# nixie_schema.net
KiCad netlist of a schematic drawn in EAGLE
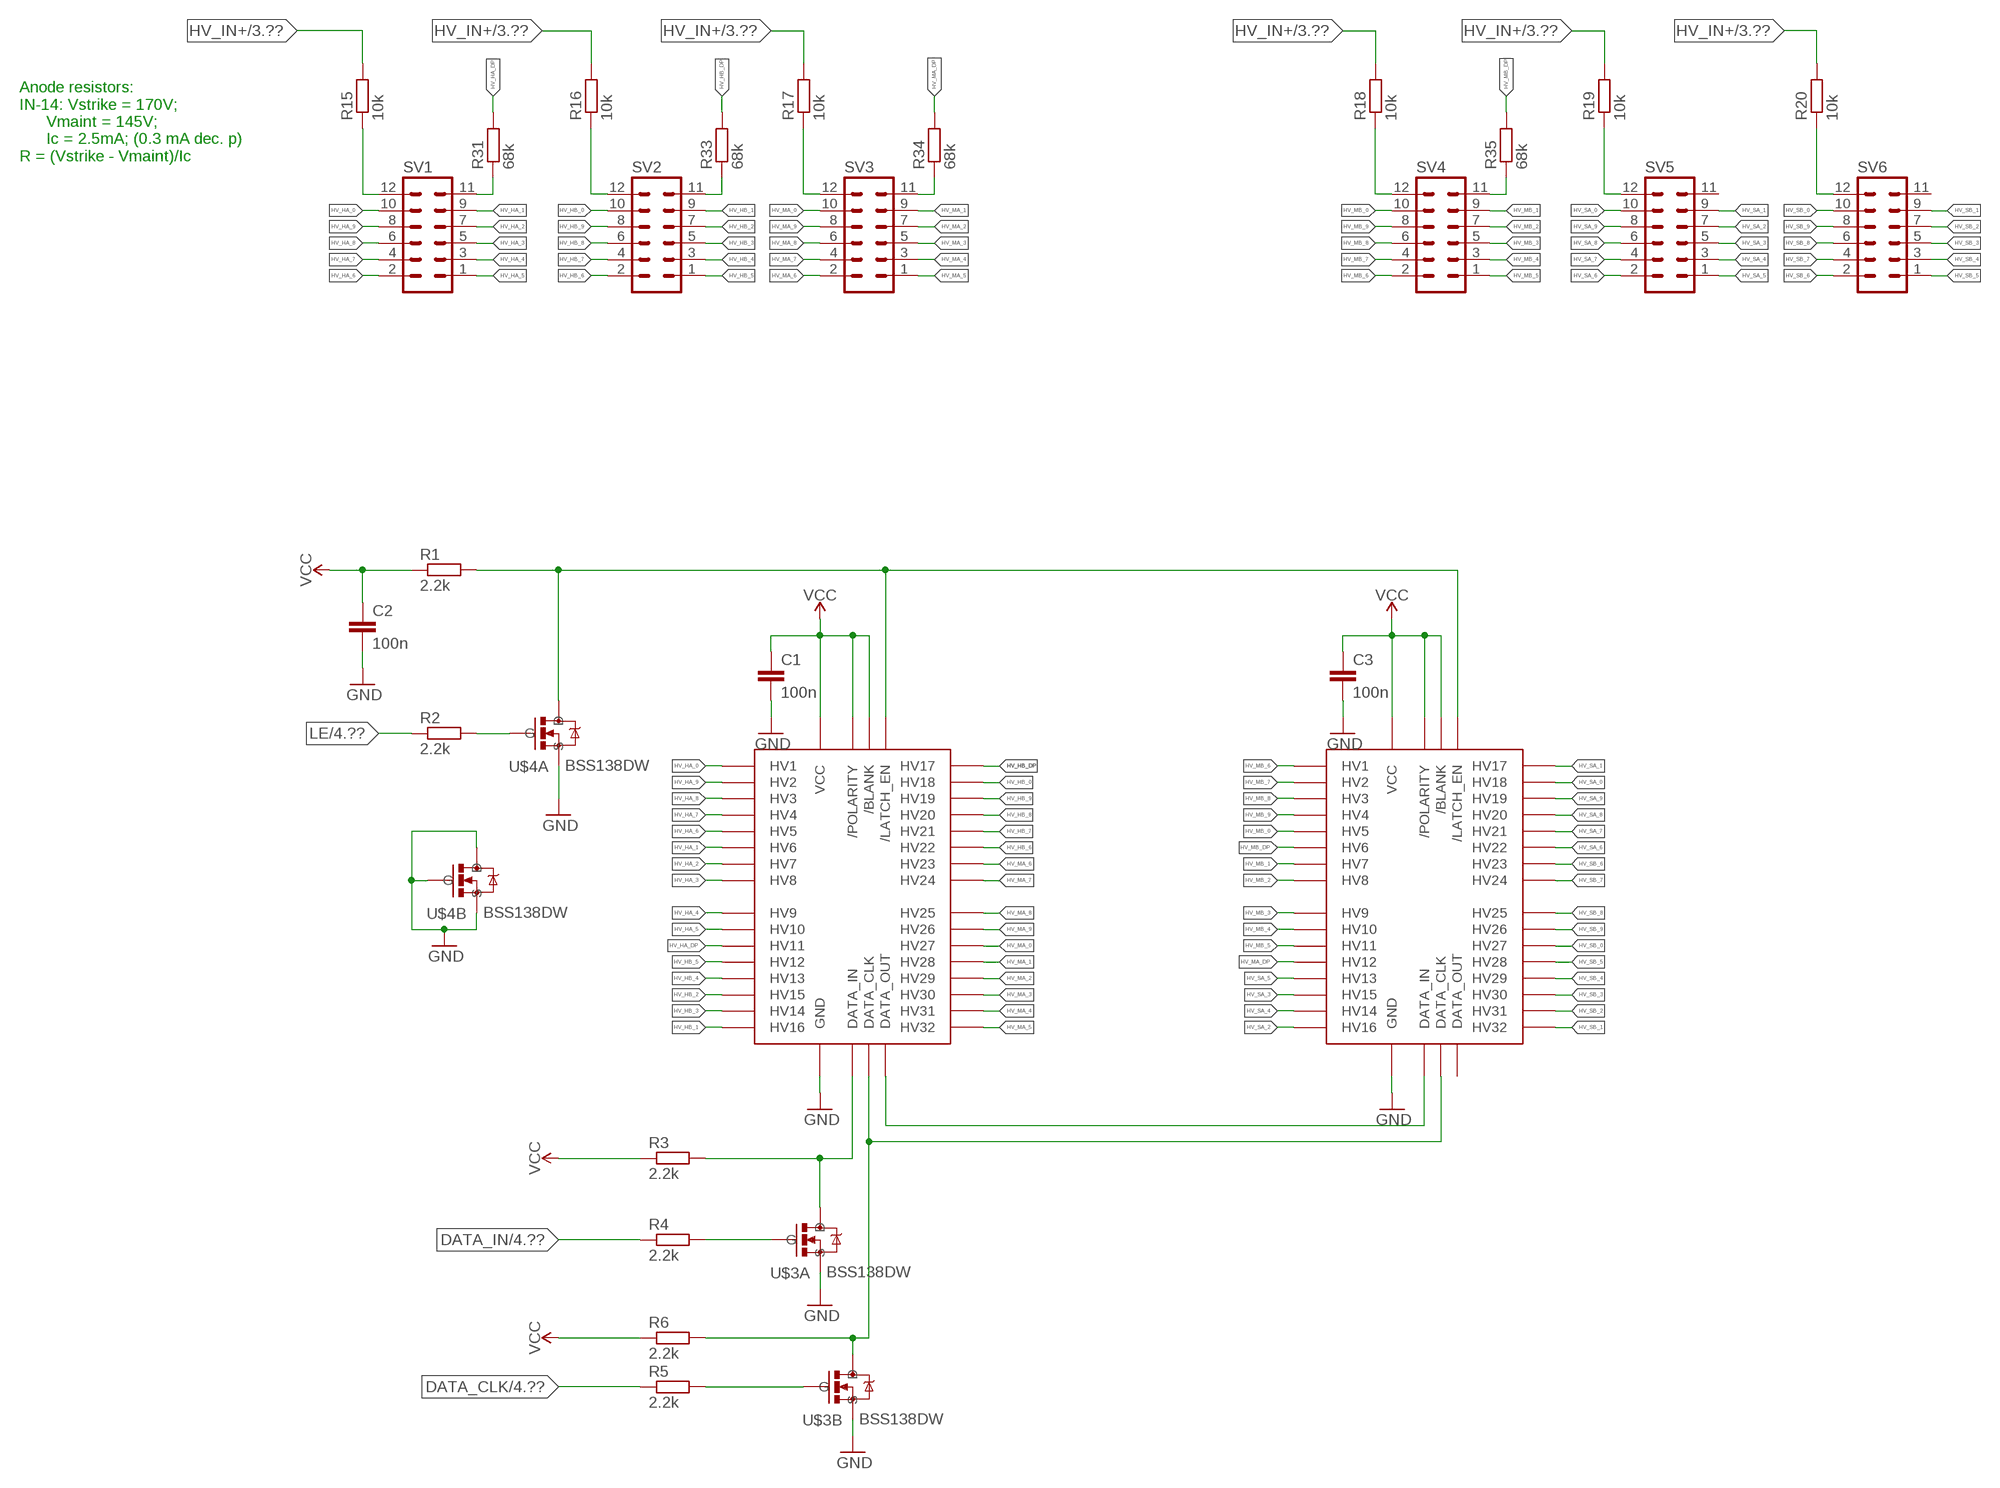
[diagram p0: schematic, sheet 1]
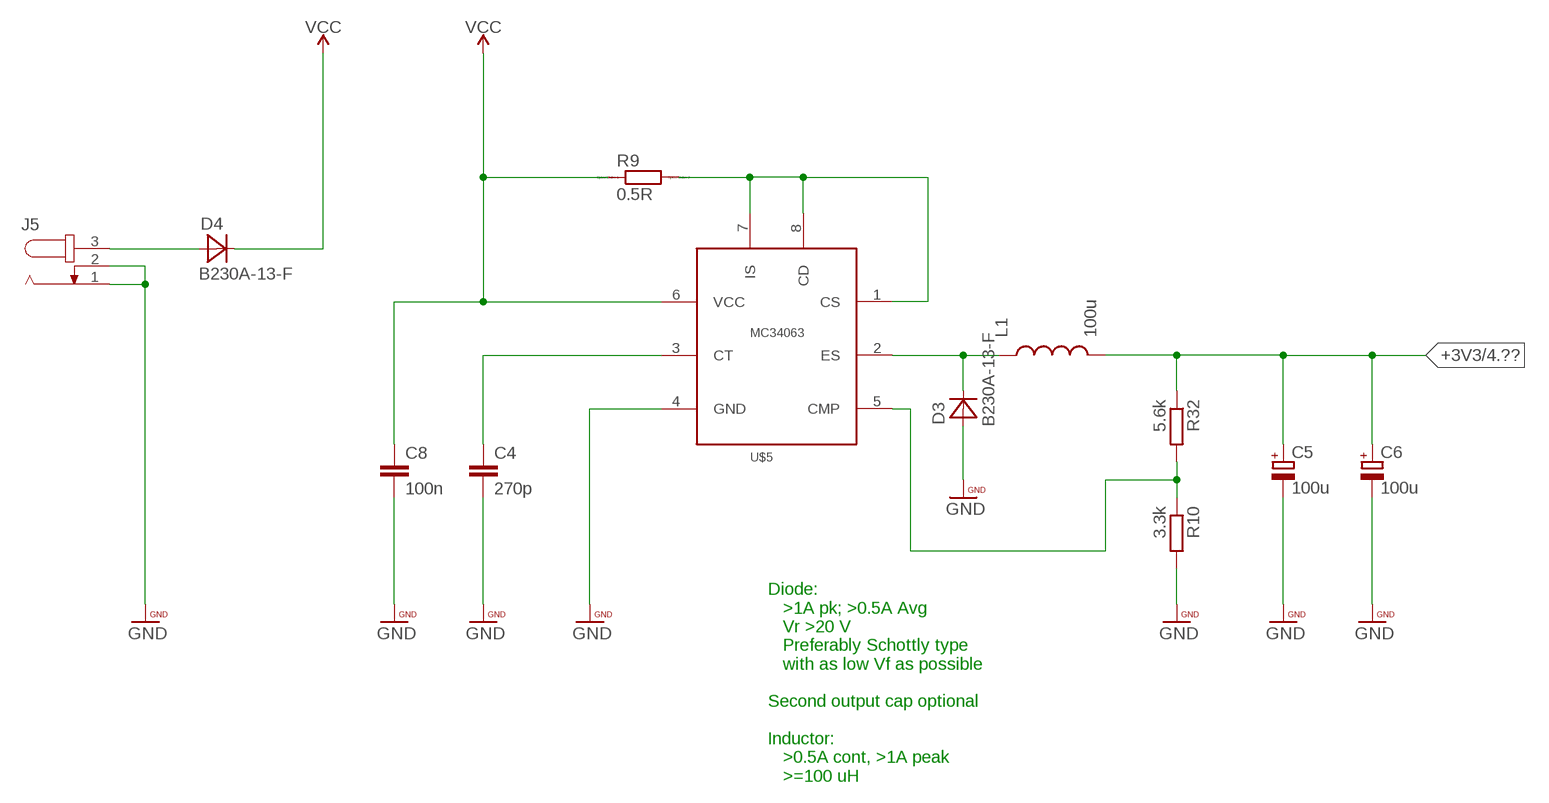
[diagram p1: schematic, sheet 2]
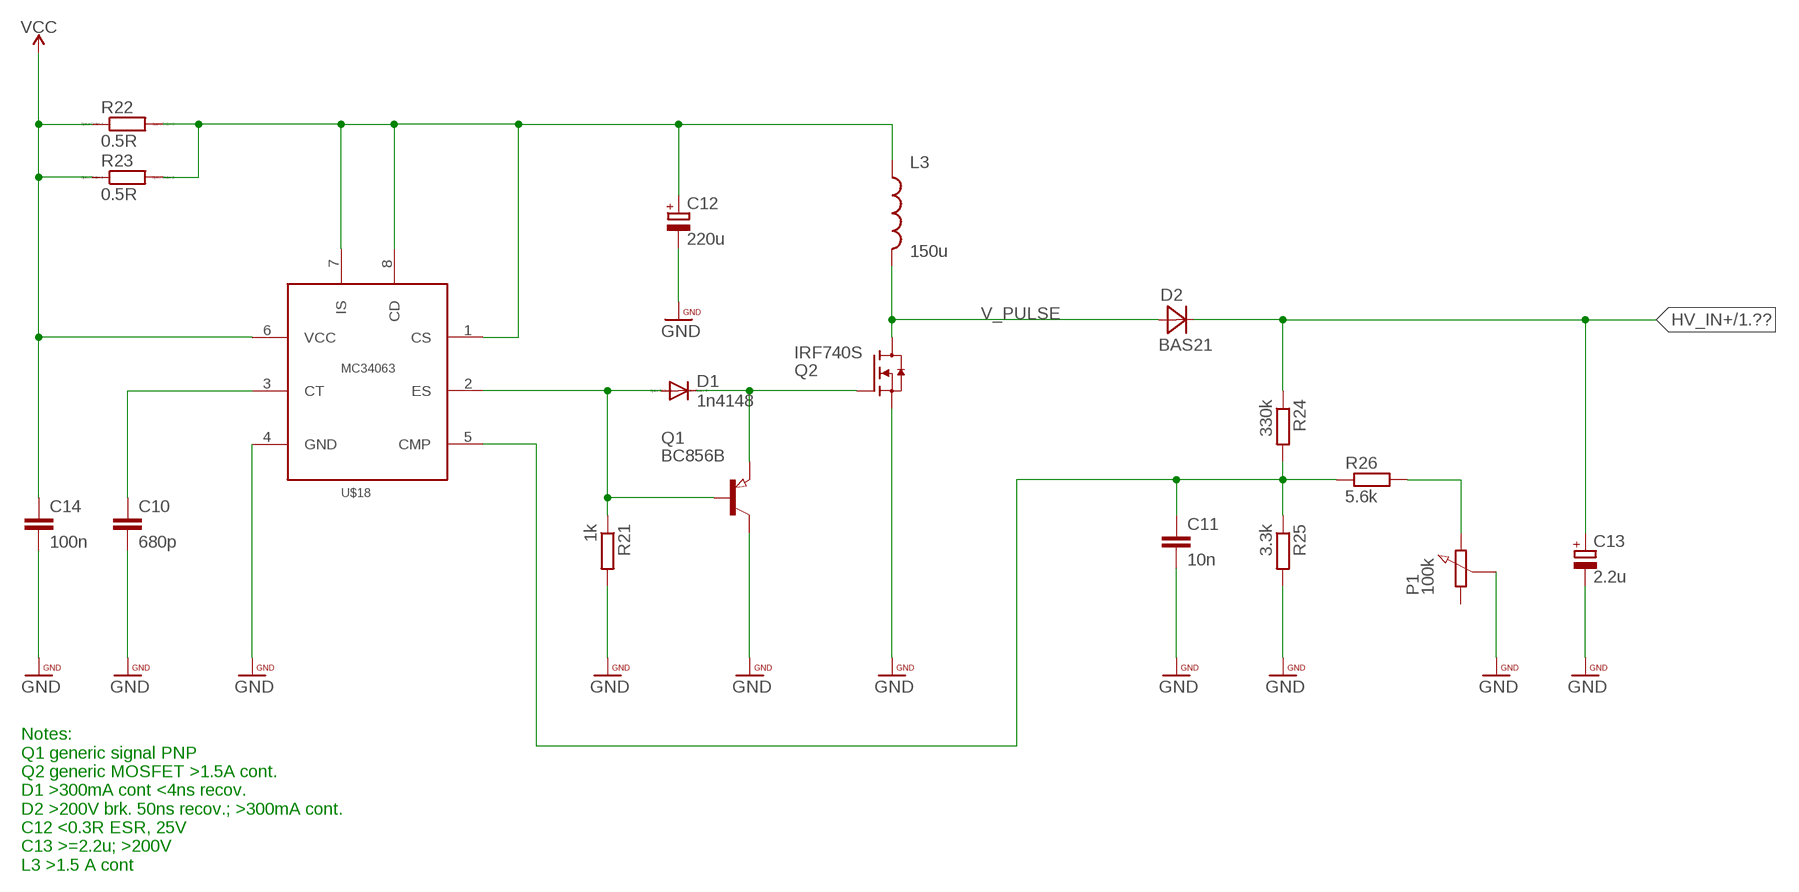
[diagram p2: schematic, sheet 3]
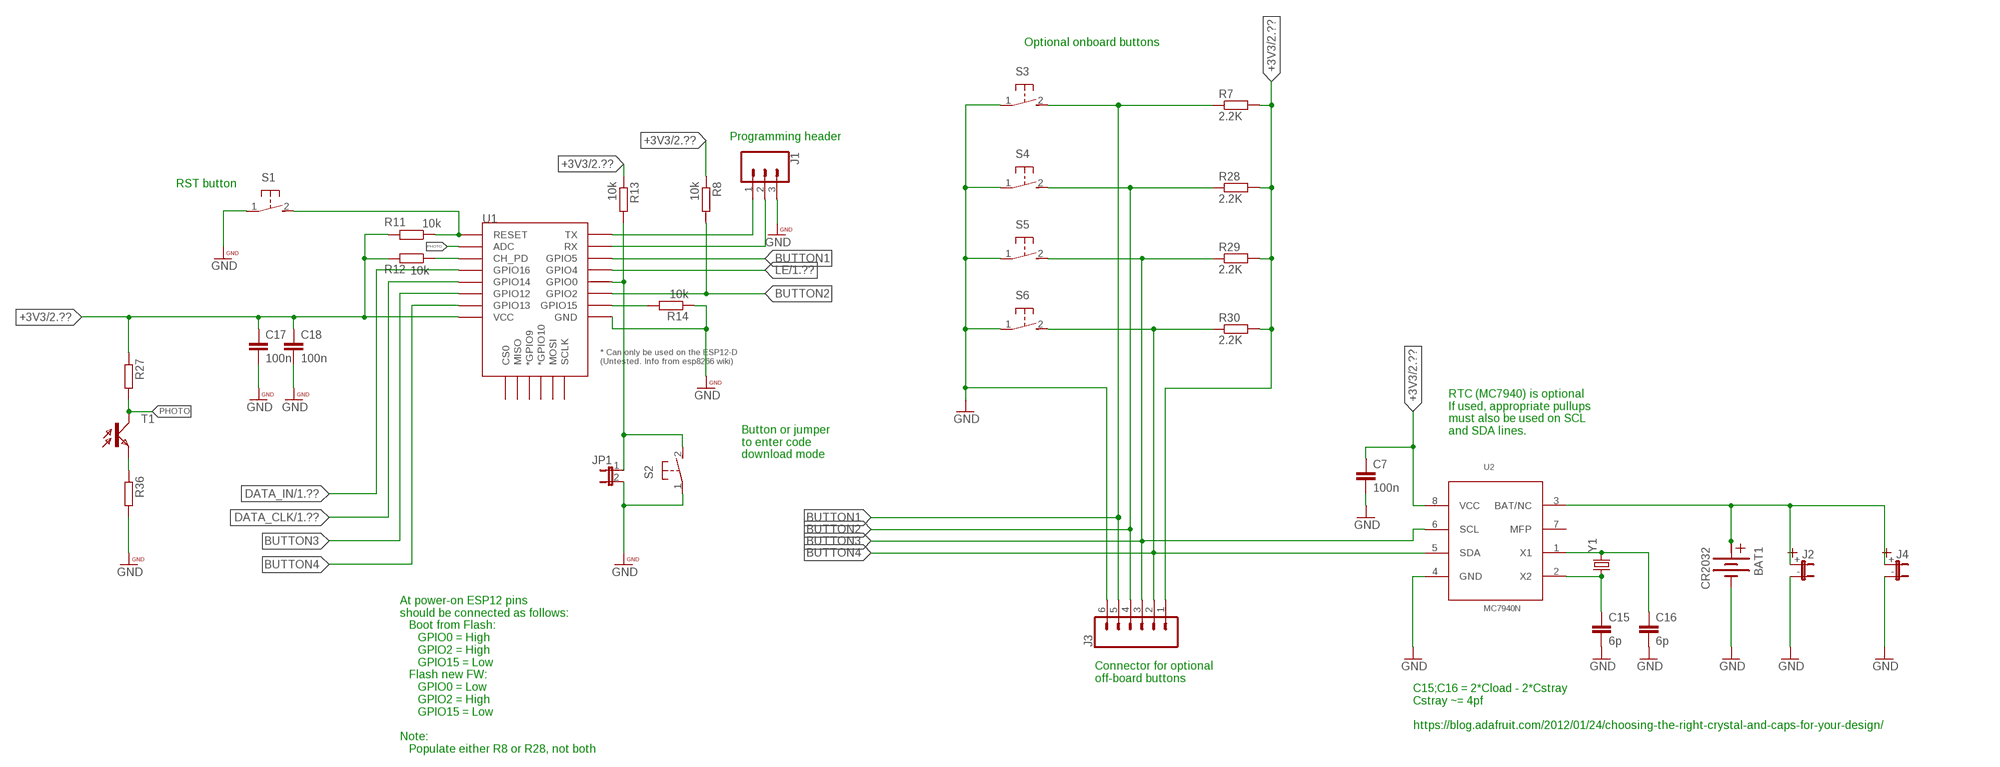
[diagram p3: schematic, sheet 4]
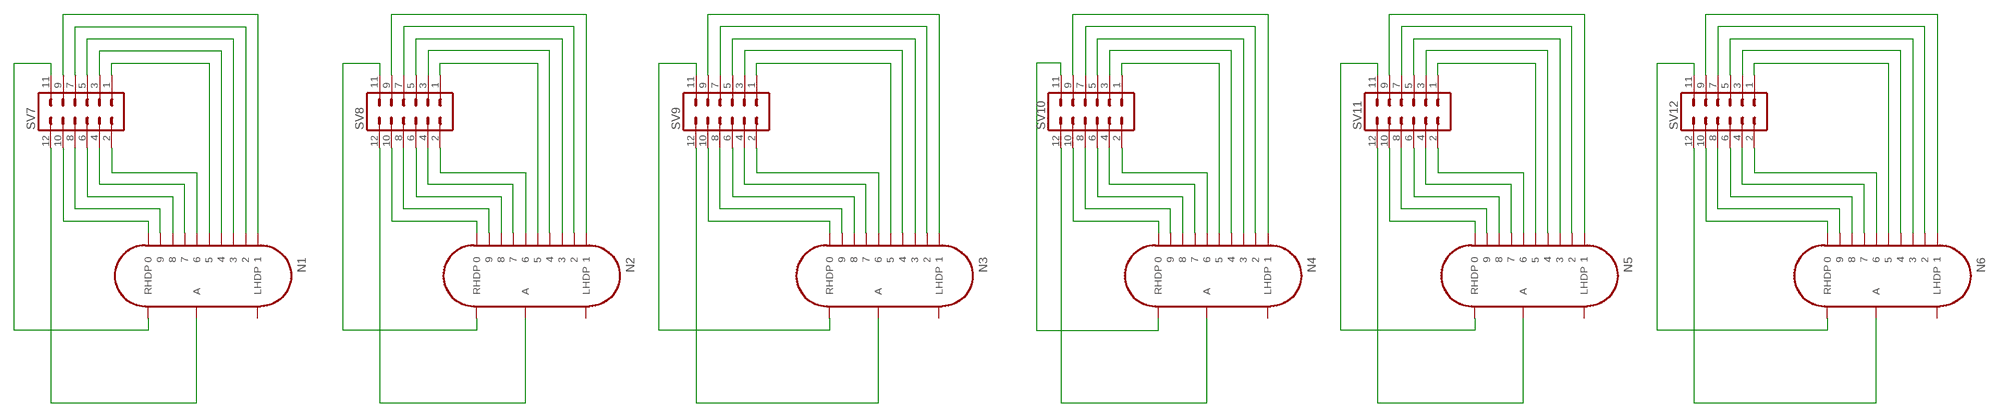
[diagram p4: schematic, sheet 5]

(export (version "E")
  (design (tool "Eeschema 10.0.6"))
  (components
    (comp (ref "C1")
      (value "100n")
      (footprint "eagle-import:C0805")
      (libsource (lib "eagle-import") (part "C-EUC0805"))
    )
    (comp (ref "C2")
      (value "100n")
      (footprint "eagle-import:C0805")
      (libsource (lib "eagle-import") (part "C-EUC0805"))
    )
    (comp (ref "C3")
      (value "100n")
      (footprint "eagle-import:C0805")
      (libsource (lib "eagle-import") (part "C-EUC0805"))
    )
    (comp (ref "R1")
      (value "2.2k")
      (footprint "eagle-import:R0603")
      (libsource (lib "eagle-import") (part "R-EU_R0603"))
    )
    (comp (ref "R2")
      (value "2.2k")
      (footprint "eagle-import:R0603")
      (libsource (lib "eagle-import") (part "R-EU_R0603"))
    )
    (comp (ref "R3")
      (value "2.2k")
      (footprint "eagle-import:R0603")
      (libsource (lib "eagle-import") (part "R-EU_R0603"))
    )
    (comp (ref "R4")
      (value "2.2k")
      (footprint "eagle-import:R0603")
      (libsource (lib "eagle-import") (part "R-EU_R0603"))
    )
    (comp (ref "R5")
      (value "2.2k")
      (footprint "eagle-import:R0603")
      (libsource (lib "eagle-import") (part "R-EU_R0603"))
    )
    (comp (ref "R6")
      (value "2.2k")
      (footprint "eagle-import:R0603")
      (libsource (lib "eagle-import") (part "R-EU_R0603"))
    )
    (comp (ref "R15")
      (value "10k")
      (footprint "eagle-import:R0603")
      (libsource (lib "eagle-import") (part "R-EU_R0603"))
    )
    (comp (ref "R16")
      (value "10k")
      (footprint "eagle-import:R0603")
      (libsource (lib "eagle-import") (part "R-EU_R0603"))
    )
    (comp (ref "R17")
      (value "10k")
      (footprint "eagle-import:R0603")
      (libsource (lib "eagle-import") (part "R-EU_R0603"))
    )
    (comp (ref "R18")
      (value "10k")
      (footprint "eagle-import:R0603")
      (libsource (lib "eagle-import") (part "R-EU_R0603"))
    )
    (comp (ref "R19")
      (value "10k")
      (footprint "eagle-import:R0603")
      (libsource (lib "eagle-import") (part "R-EU_R0603"))
    )
    (comp (ref "R20")
      (value "10k")
      (footprint "eagle-import:R0603")
      (libsource (lib "eagle-import") (part "R-EU_R0603"))
    )
    (comp (ref "R31")
      (value "68k")
      (footprint "eagle-import:R0603")
      (libsource (lib "eagle-import") (part "R-EU_R0603"))
    )
    (comp (ref "R33")
      (value "68k")
      (footprint "eagle-import:R0603")
      (libsource (lib "eagle-import") (part "R-EU_R0603"))
    )
    (comp (ref "R34")
      (value "68k")
      (footprint "eagle-import:R0603")
      (libsource (lib "eagle-import") (part "R-EU_R0603"))
    )
    (comp (ref "R35")
      (value "68k")
      (footprint "eagle-import:R0603")
      (libsource (lib "eagle-import") (part "R-EU_R0603"))
    )
    (comp (ref "SV1")
      (value "MA06-2")
      (footprint "eagle-import:MA06-2")
      (libsource (lib "eagle-import") (part "MA06-2"))
    )
    (comp (ref "SV2")
      (value "MA06-2")
      (footprint "eagle-import:MA06-2")
      (libsource (lib "eagle-import") (part "MA06-2"))
    )
    (comp (ref "SV3")
      (value "MA06-2")
      (footprint "eagle-import:MA06-2")
      (libsource (lib "eagle-import") (part "MA06-2"))
    )
    (comp (ref "SV4")
      (value "MA06-2")
      (footprint "eagle-import:MA06-2")
      (libsource (lib "eagle-import") (part "MA06-2"))
    )
    (comp (ref "SV5")
      (value "MA06-2")
      (footprint "eagle-import:MA06-2")
      (libsource (lib "eagle-import") (part "MA06-2"))
    )
    (comp (ref "SV6")
      (value "MA06-2")
      (footprint "eagle-import:MA06-2")
      (libsource (lib "eagle-import") (part "MA06-2"))
    )
    (comp (ref "U$1")
      (value "HV5522")
      (footprint "eagle-import:CQFP-44")
      (libsource (lib "eagle-import") (part "HV5522"))
    )
    (comp (ref "U$2")
      (value "HV5522")
      (footprint "eagle-import:CQFP-44")
      (libsource (lib "eagle-import") (part "HV5522"))
    )
    (comp (ref "U$3")
      (value "BSS138DW")
      (footprint "eagle-import:SOT-363")
      (libsource (lib "eagle-import") (part "BSS138DW"))
    )
    (comp (ref "U$4")
      (value "BSS138DW")
      (footprint "eagle-import:SOT-363")
      (libsource (lib "eagle-import") (part "BSS138DW"))
    )
    (comp (ref "BAT1")
      (value "CR2032")
      (footprint "eagle-import:CR2032")
      (libsource (lib "eagle-import") (part "CR2032"))
    )
    (comp (ref "C7")
      (value "100n")
      (footprint "eagle-import:C0805")
      (libsource (lib "eagle-import") (part "C-EUC0805"))
    )
    (comp (ref "C15")
      (value "6p")
      (footprint "eagle-import:C0805")
      (libsource (lib "eagle-import") (part "C-EUC0805"))
    )
    (comp (ref "C16")
      (value "6p")
      (footprint "eagle-import:C0805")
      (libsource (lib "eagle-import") (part "C-EUC0805"))
    )
    (comp (ref "C17")
      (value "100n")
      (footprint "eagle-import:C0805")
      (libsource (lib "eagle-import") (part "C-EUC0805"))
    )
    (comp (ref "C18")
      (value "100n")
      (footprint "eagle-import:C0805")
      (libsource (lib "eagle-import") (part "C-EUC0805"))
    )
    (comp (ref "J1")
      (value "CONN_03")
      (footprint "eagle-import:1X03")
      (libsource (lib "eagle-import") (part "CONN_03"))
    )
    (comp (ref "J2")
      (value "RTC_CONSMD")
      (footprint "eagle-import:PICOBLADE_SMD_2")
      (libsource (lib "eagle-import") (part "RTC_CONSMD"))
    )
    (comp (ref "J3")
      (value "CONN_06NO_SILK_FEMALE_PTH")
      (footprint "eagle-import:1X06_NO_SILK")
      (libsource (lib "eagle-import") (part "CONN_06NO_SILK_FEMALE_PTH"))
    )
    (comp (ref "J4")
      (value "RTC_CONTHT")
      (footprint "eagle-import:PICOBLADE_THT_2")
      (libsource (lib "eagle-import") (part "RTC_CONTHT"))
    )
    (comp (ref "JP1")
      (value "JUMPER2")
      (footprint "eagle-import:JUMPER2")
      (libsource (lib "eagle-import") (part "JUMPER2"))
    )
    (comp (ref "R7")
      (value "2.2K")
      (footprint "eagle-import:R0603")
      (libsource (lib "eagle-import") (part "R-EU_R0603"))
    )
    (comp (ref "R8")
      (value "10k")
      (footprint "eagle-import:R0603")
      (libsource (lib "eagle-import") (part "resistor_R-EU_R0603"))
    )
    (comp (ref "R11")
      (value "10k")
      (footprint "eagle-import:R0603")
      (libsource (lib "eagle-import") (part "resistor_R-EU_R0603"))
    )
    (comp (ref "R12")
      (value "10k")
      (footprint "eagle-import:R0603")
      (libsource (lib "eagle-import") (part "resistor_R-EU_R0603"))
    )
    (comp (ref "R13")
      (value "10k")
      (footprint "eagle-import:R0603")
      (libsource (lib "eagle-import") (part "resistor_R-EU_R0603"))
    )
    (comp (ref "R14")
      (value "10k")
      (footprint "eagle-import:R0603")
      (libsource (lib "eagle-import") (part "resistor_R-EU_R0603"))
    )
    (comp (ref "R27")
      (value "R-EU_R0603")
      (footprint "eagle-import:R0603")
      (libsource (lib "eagle-import") (part "resistor_R-EU_R0603"))
    )
    (comp (ref "R28")
      (value "2.2K")
      (footprint "eagle-import:R0603")
      (libsource (lib "eagle-import") (part "R-EU_R0603"))
    )
    (comp (ref "R29")
      (value "2.2K")
      (footprint "eagle-import:R0603")
      (libsource (lib "eagle-import") (part "R-EU_R0603"))
    )
    (comp (ref "R30")
      (value "2.2K")
      (footprint "eagle-import:R0603")
      (libsource (lib "eagle-import") (part "R-EU_R0603"))
    )
    (comp (ref "R36")
      (value "R-EU_R0603")
      (footprint "eagle-import:R0603")
      (libsource (lib "eagle-import") (part "resistor_R-EU_R0603"))
    )
    (comp (ref "S1")
      (value "31-XX")
      (footprint "eagle-import:B3F-31XX")
      (fields (field (name "MPN") "B3F-3100"))
      (libsource (lib "eagle-import") (part "31-XX"))
    )
    (comp (ref "S2")
      (value "31-XX")
      (footprint "eagle-import:B3F-31XX")
      (fields (field (name "MPN") "B3F-3100"))
      (libsource (lib "eagle-import") (part "31-XX"))
    )
    (comp (ref "S3")
      (value "31-XX")
      (footprint "eagle-import:B3F-31XX")
      (fields (field (name "MPN") "B3F-3100"))
      (libsource (lib "eagle-import") (part "31-XX"))
    )
    (comp (ref "S4")
      (value "31-XX")
      (footprint "eagle-import:B3F-31XX")
      (fields (field (name "MPN") "B3F-3100"))
      (libsource (lib "eagle-import") (part "31-XX"))
    )
    (comp (ref "S5")
      (value "31-XX")
      (footprint "eagle-import:B3F-31XX")
      (fields (field (name "MPN") "B3F-3100"))
      (libsource (lib "eagle-import") (part "31-XX"))
    )
    (comp (ref "S6")
      (value "31-XX")
      (footprint "eagle-import:B3F-31XX")
      (fields (field (name "MPN") "B3F-3100"))
      (libsource (lib "eagle-import") (part "31-XX"))
    )
    (comp (ref "T1")
      (value "PHOTO_TRANS")
      (footprint "eagle-import:C0805K")
      (libsource (lib "eagle-import") (part "PHOTO_TRANS"))
    )
    (comp (ref "U1")
      (value "ESP12ESMD")
      (footprint "eagle-import:ESP12E-SMD")
      (libsource (lib "eagle-import") (part "ESP12ESMD"))
    )
    (comp (ref "U2")
      (value "MC7940N")
      (footprint "eagle-import:SOIC8-N_MC")
      (libsource (lib "eagle-import") (part "MC7940N"))
    )
    (comp (ref "Y1")
      (value "ECS-.327-7-34B")
      (footprint "eagle-import:CRYSTAL_PACK")
      (libsource (lib "eagle-import") (part "ECS-.327-7-34B"))
    )
    (comp (ref "C4")
      (value "270p")
      (footprint "eagle-import:C0805")
      (libsource (lib "eagle-import") (part "C-EUC0805"))
    )
    (comp (ref "C5")
      (value "100u")
      (footprint "eagle-import:153CLV-1014")
      (libsource (lib "eagle-import") (part "CPOL-EU153CLV-1014"))
    )
    (comp (ref "C6")
      (value "100u")
      (footprint "eagle-import:153CLV-1014")
      (libsource (lib "eagle-import") (part "CPOL-EU153CLV-1014"))
    )
    (comp (ref "C8")
      (value "100n")
      (footprint "eagle-import:C0805")
      (libsource (lib "eagle-import") (part "C-EUC0805"))
    )
    (comp (ref "D3")
      (value "B230A-13-F")
      (footprint "eagle-import:SMA_SMB")
      (libsource (lib "eagle-import") (part "B230A-13-F"))
    )
    (comp (ref "D4")
      (value "B230A-13-F")
      (footprint "eagle-import:SMA_SMB")
      (libsource (lib "eagle-import") (part "B230A-13-F"))
    )
    (comp (ref "J5")
      (value "JACK-PLUG0")
      (footprint "eagle-import:SPC4077")
      (libsource (lib "eagle-import") (part "JACK-PLUG0"))
    )
    (comp (ref "L1")
      (value "100u")
      (footprint "eagle-import:INDUCTOR_PACKAGE")
      (libsource (lib "eagle-import") (part "HM78D-128151KLFTR"))
    )
    (comp (ref "R9")
      (value "0.5R")
      (footprint "eagle-import:R1210")
      (libsource (lib "eagle-import") (part "RR1210"))
    )
    (comp (ref "R10")
      (value "3.3k")
      (footprint "eagle-import:R0603")
      (libsource (lib "eagle-import") (part "resistor_R-EU_R0603"))
    )
    (comp (ref "R32")
      (value "5.6k")
      (footprint "eagle-import:R0603")
      (libsource (lib "eagle-import") (part "resistor_R-EU_R0603"))
    )
    (comp (ref "U$5")
      (value "MC34063")
      (footprint "eagle-import:SOIC08")
      (libsource (lib "eagle-import") (part "MC34063"))
    )
    (comp (ref "N1")
      (value "IN-14_FIXED")
      (footprint "eagle-import:IN-14")
      (libsource (lib "eagle-import") (part "IN-14_FIXED"))
    )
    (comp (ref "N2")
      (value "IN-14_FIXED")
      (footprint "eagle-import:IN-14")
      (libsource (lib "eagle-import") (part "IN-14_FIXED"))
    )
    (comp (ref "N3")
      (value "IN-14_FIXED")
      (footprint "eagle-import:IN-14")
      (libsource (lib "eagle-import") (part "IN-14_FIXED"))
    )
    (comp (ref "N4")
      (value "IN-14_FIXED")
      (footprint "eagle-import:IN-14")
      (libsource (lib "eagle-import") (part "IN-14_FIXED"))
    )
    (comp (ref "N5")
      (value "IN-14_FIXED")
      (footprint "eagle-import:IN-14")
      (libsource (lib "eagle-import") (part "IN-14_FIXED"))
    )
    (comp (ref "N6")
      (value "IN-14_FIXED")
      (footprint "eagle-import:IN-14")
      (libsource (lib "eagle-import") (part "IN-14_FIXED"))
    )
    (comp (ref "SV7")
      (value "MA06-2")
      (footprint "eagle-import:MA06-2")
      (libsource (lib "eagle-import") (part "MA06-2"))
    )
    (comp (ref "SV8")
      (value "MA06-2")
      (footprint "eagle-import:MA06-2")
      (libsource (lib "eagle-import") (part "MA06-2"))
    )
    (comp (ref "SV9")
      (value "MA06-2")
      (footprint "eagle-import:MA06-2")
      (libsource (lib "eagle-import") (part "MA06-2"))
    )
    (comp (ref "SV10")
      (value "MA06-2")
      (footprint "eagle-import:MA06-2")
      (libsource (lib "eagle-import") (part "MA06-2"))
    )
    (comp (ref "SV11")
      (value "MA06-2")
      (footprint "eagle-import:MA06-2")
      (libsource (lib "eagle-import") (part "MA06-2"))
    )
    (comp (ref "SV12")
      (value "MA06-2")
      (footprint "eagle-import:MA06-2")
      (libsource (lib "eagle-import") (part "MA06-2"))
    )
    (comp (ref "C10")
      (value "680p")
      (footprint "eagle-import:C0805")
      (libsource (lib "eagle-import") (part "C-EUC0805"))
    )
    (comp (ref "C11")
      (value "10n")
      (footprint "eagle-import:C0805")
      (libsource (lib "eagle-import") (part "C-EUC0805"))
    )
    (comp (ref "C12")
      (value "220u")
      (footprint "eagle-import:153CLV-1014")
      (libsource (lib "eagle-import") (part "CPOL-EU153CLV-1014"))
    )
    (comp (ref "C13")
      (value "2.2u")
      (footprint "eagle-import:153CLV-1014")
      (libsource (lib "eagle-import") (part "CPOL-EU153CLV-1014"))
    )
    (comp (ref "C14")
      (value "100n")
      (footprint "eagle-import:C0805")
      (libsource (lib "eagle-import") (part "C-EUC0805"))
    )
    (comp (ref "D1")
      (value "1n4148")
      (footprint "eagle-import:SOD123")
      (libsource (lib "eagle-import") (part "DIODE-SOD123"))
    )
    (comp (ref "D2")
      (value "BAS21")
      (footprint "eagle-import:SOT23")
      (libsource (lib "eagle-import") (part "BAS21"))
    )
    (comp (ref "L3")
      (value "150u")
      (footprint "eagle-import:INDUCTOR_PACKAGE")
      (libsource (lib "eagle-import") (part "HM78D-128151KLFTR"))
    )
    (comp (ref "P1")
      (value "100k")
      (footprint "eagle-import:UNI_POT_SMD")
      (libsource (lib "eagle-import") (part "UNIVERSAL-POTENTIOMETER_SMD"))
    )
    (comp (ref "Q1")
      (value "BC856B")
      (footprint "eagle-import:SOT23")
      (libsource (lib "eagle-import") (part "BC856B"))
    )
    (comp (ref "Q2")
      (value "IRF740S")
      (footprint "eagle-import:D2PACK")
      (libsource (lib "eagle-import") (part "IRF740S"))
    )
    (comp (ref "R21")
      (value "1k")
      (footprint "eagle-import:R0603")
      (libsource (lib "eagle-import") (part "resistor_R-EU_R0603"))
    )
    (comp (ref "R22")
      (value "0.5R")
      (footprint "eagle-import:R1210")
      (libsource (lib "eagle-import") (part "RR1210"))
    )
    (comp (ref "R23")
      (value "0.5R")
      (footprint "eagle-import:R1210")
      (libsource (lib "eagle-import") (part "RR1210"))
    )
    (comp (ref "R24")
      (value "330k")
      (footprint "eagle-import:R0603")
      (libsource (lib "eagle-import") (part "resistor_R-EU_R0603"))
    )
    (comp (ref "R25")
      (value "3.3k")
      (footprint "eagle-import:R0603")
      (libsource (lib "eagle-import") (part "resistor_R-EU_R0603"))
    )
    (comp (ref "R26")
      (value "5.6k")
      (footprint "eagle-import:R0603")
      (libsource (lib "eagle-import") (part "resistor_R-EU_R0603"))
    )
    (comp (ref "U$18")
      (value "MC34063")
      (footprint "eagle-import:SOIC08")
      (libsource (lib "eagle-import") (part "MC34063"))
    )
  )
  (nets
    (net (code "1") (name "+") (class "Default")
      (node (ref "BAT1") (pin "+_2") (pinfunction "+_+_2") (pintype "power_in"))
    )
    (net (code "2") (name "+3V3") (class "Default")
      (node (ref "C17") (pin "1") (pinfunction "1_1") (pintype "passive"))
      (node (ref "C18") (pin "1") (pinfunction "1_1") (pintype "passive"))
      (node (ref "C5") (pin "+") (pinfunction "+_+") (pintype "passive"))
      (node (ref "C6") (pin "+") (pinfunction "+_+") (pintype "passive"))
      (node (ref "C7") (pin "1") (pinfunction "1_1") (pintype "passive"))
      (node (ref "J3") (pin "1") (pinfunction "1_1") (pintype "passive"))
      (node (ref "L1") (pin "P$2") (pinfunction "2_P$2") (pintype "passive"))
      (node (ref "R11") (pin "2") (pinfunction "2_2") (pintype "passive"))
      (node (ref "R12") (pin "2") (pinfunction "2_2") (pintype "passive"))
      (node (ref "R13") (pin "1") (pinfunction "1_1") (pintype "passive"))
      (node (ref "R27") (pin "1") (pinfunction "1_1") (pintype "passive"))
      (node (ref "R28") (pin "2") (pinfunction "2_2") (pintype "passive"))
      (node (ref "R29") (pin "2") (pinfunction "2_2") (pintype "passive"))
      (node (ref "R30") (pin "2") (pinfunction "2_2") (pintype "passive"))
      (node (ref "R32") (pin "1") (pinfunction "1_1") (pintype "passive"))
      (node (ref "R7") (pin "2") (pinfunction "2_2") (pintype "passive"))
      (node (ref "R8") (pin "1") (pinfunction "1_1") (pintype "passive"))
      (node (ref "U1") (pin "VCC") (pinfunction "VCC_VCC") (pintype "bidirectional"))
      (node (ref "U2") (pin "8") (pinfunction "VCC_8") (pintype "bidirectional"))
    )
    (net (code "3") (name "BUTTON1") (class "Default")
      (node (ref "J3") (pin "5") (pinfunction "5_5") (pintype "passive"))
      (node (ref "R7") (pin "1") (pinfunction "1_1") (pintype "passive"))
      (node (ref "S3") (pin "2") (pinfunction "S_2") (pintype "passive"))
      (node (ref "U1") (pin "GPIO5") (pinfunction "GPIO5_GPIO5") (pintype "bidirectional"))
    )
    (net (code "4") (name "BUTTON2") (class "Default")
      (node (ref "J3") (pin "4") (pinfunction "4_4") (pintype "passive"))
      (node (ref "R28") (pin "1") (pinfunction "1_1") (pintype "passive"))
      (node (ref "R8") (pin "2") (pinfunction "2_2") (pintype "passive"))
      (node (ref "S4") (pin "2") (pinfunction "S_2") (pintype "passive"))
      (node (ref "U1") (pin "GPIO2") (pinfunction "GPIO2_GPIO2") (pintype "bidirectional"))
    )
    (net (code "5") (name "BUTTON3") (class "Default")
      (node (ref "J3") (pin "3") (pinfunction "3_3") (pintype "passive"))
      (node (ref "R29") (pin "1") (pinfunction "1_1") (pintype "passive"))
      (node (ref "S5") (pin "2") (pinfunction "S_2") (pintype "passive"))
      (node (ref "U1") (pin "GPIO12") (pinfunction "GPIO12_GPIO12") (pintype "bidirectional"))
      (node (ref "U2") (pin "6") (pinfunction "SCL_6") (pintype "bidirectional"))
    )
    (net (code "6") (name "BUTTON4") (class "Default")
      (node (ref "J3") (pin "2") (pinfunction "2_2") (pintype "passive"))
      (node (ref "R30") (pin "1") (pinfunction "1_1") (pintype "passive"))
      (node (ref "S6") (pin "2") (pinfunction "S_2") (pintype "passive"))
      (node (ref "U1") (pin "GPIO13") (pinfunction "GPIO13_GPIO13") (pintype "bidirectional"))
      (node (ref "U2") (pin "5") (pinfunction "SDA_5") (pintype "bidirectional"))
    )
    (net (code "7") (name "DATA_CLK") (class "Default")
      (node (ref "R5") (pin "1") (pinfunction "1_1") (pintype "passive"))
      (node (ref "U1") (pin "GPIO14") (pinfunction "GPIO14_GPIO14") (pintype "bidirectional"))
    )
    (net (code "8") (name "DATA_IN") (class "Default")
      (node (ref "R4") (pin "1") (pinfunction "1_1") (pintype "passive"))
      (node (ref "U1") (pin "GPIO16") (pinfunction "GPIO16_GPIO16") (pintype "bidirectional"))
    )
    (net (code "9") (name "GND") (class "Default")
      (node (ref "BAT1") (pin "-") (pinfunction "-_-") (pintype "power_in"))
      (node (ref "C1") (pin "2") (pinfunction "2_2") (pintype "passive"))
      (node (ref "C10") (pin "2") (pinfunction "2_2") (pintype "passive"))
      (node (ref "C11") (pin "2") (pinfunction "2_2") (pintype "passive"))
      (node (ref "C12") (pin "-") (pinfunction "-_-") (pintype "passive"))
      (node (ref "C13") (pin "-") (pinfunction "-_-") (pintype "passive"))
      (node (ref "C14") (pin "2") (pinfunction "2_2") (pintype "passive"))
      (node (ref "C15") (pin "2") (pinfunction "2_2") (pintype "passive"))
      (node (ref "C16") (pin "2") (pinfunction "2_2") (pintype "passive"))
      (node (ref "C17") (pin "2") (pinfunction "2_2") (pintype "passive"))
      (node (ref "C18") (pin "2") (pinfunction "2_2") (pintype "passive"))
      (node (ref "C2") (pin "2") (pinfunction "2_2") (pintype "passive"))
      (node (ref "C3") (pin "2") (pinfunction "2_2") (pintype "passive"))
      (node (ref "C4") (pin "2") (pinfunction "2_2") (pintype "passive"))
      (node (ref "C5") (pin "-") (pinfunction "-_-") (pintype "passive"))
      (node (ref "C6") (pin "-") (pinfunction "-_-") (pintype "passive"))
      (node (ref "C7") (pin "2") (pinfunction "2_2") (pintype "passive"))
      (node (ref "C8") (pin "2") (pinfunction "2_2") (pintype "passive"))
      (node (ref "D3") (pin "A") (pinfunction "A_A") (pintype "passive"))
      (node (ref "J1") (pin "3") (pinfunction "3_3") (pintype "passive"))
      (node (ref "J2") (pin "-") (pinfunction "-_-") (pintype "passive"))
      (node (ref "J3") (pin "6") (pinfunction "6_6") (pintype "passive"))
      (node (ref "J4") (pin "-") (pinfunction "-_-") (pintype "passive"))
      (node (ref "J5") (pin "1") (pinfunction "1_1") (pintype "passive"))
      (node (ref "J5") (pin "2") (pinfunction "2_2") (pintype "passive"))
      (node (ref "JP1") (pin "2") (pinfunction "2_2") (pintype "passive"))
      (node (ref "P1") (pin "P$2") (pinfunction "WIPER_P$2") (pintype "passive"))
      (node (ref "Q1") (pin "3") (pinfunction "C_3") (pintype "passive"))
      (node (ref "Q2") (pin "3") (pinfunction "S_3") (pintype "passive"))
      (node (ref "R10") (pin "2") (pinfunction "2_2") (pintype "passive"))
      (node (ref "R14") (pin "1") (pinfunction "1_1") (pintype "passive"))
      (node (ref "R21") (pin "2") (pinfunction "2_2") (pintype "passive"))
      (node (ref "R25") (pin "2") (pinfunction "2_2") (pintype "passive"))
      (node (ref "R36") (pin "2") (pinfunction "2_2") (pintype "passive"))
      (node (ref "S1") (pin "1") (pinfunction "P_1") (pintype "passive"))
      (node (ref "S2") (pin "1") (pinfunction "P_1") (pintype "passive"))
      (node (ref "S3") (pin "1") (pinfunction "P_1") (pintype "passive"))
      (node (ref "S4") (pin "1") (pinfunction "P_1") (pintype "passive"))
      (node (ref "S5") (pin "1") (pinfunction "P_1") (pintype "passive"))
      (node (ref "S6") (pin "1") (pinfunction "P_1") (pintype "passive"))
      (node (ref "U$1") (pin "24") (pinfunction "GND_24") (pintype "power_in"))
      (node (ref "U$1") (pin "25") (pinfunction "GND_25") (pintype "power_in"))
      (node (ref "U$1") (pin "26") (pinfunction "GND_26") (pintype "power_in"))
      (node (ref "U$1") (pin "29") (pinfunction "GND_29") (pintype "power_in"))
      (node (ref "U$1") (pin "34") (pinfunction "GND_34") (pintype "power_in"))
      (node (ref "U$18") (pin "4") (pinfunction "GND_4") (pintype "bidirectional"))
      (node (ref "U$2") (pin "24") (pinfunction "GND_24") (pintype "power_in"))
      (node (ref "U$2") (pin "25") (pinfunction "GND_25") (pintype "power_in"))
      (node (ref "U$2") (pin "26") (pinfunction "GND_26") (pintype "power_in"))
      (node (ref "U$2") (pin "29") (pinfunction "GND_29") (pintype "power_in"))
      (node (ref "U$2") (pin "34") (pinfunction "GND_34") (pintype "power_in"))
      (node (ref "U$3") (pin "1") (pinfunction "S_1") (pintype "passive"))
      (node (ref "U$3") (pin "4") (pinfunction "S_4") (pintype "passive"))
      (node (ref "U$4") (pin "1") (pinfunction "S_1") (pintype "passive"))
      (node (ref "U$4") (pin "3") (pinfunction "D_3") (pintype "passive"))
      (node (ref "U$4") (pin "4") (pinfunction "S_4") (pintype "passive"))
      (node (ref "U$4") (pin "5") (pinfunction "G_5") (pintype "passive"))
      (node (ref "U$5") (pin "4") (pinfunction "GND_4") (pintype "bidirectional"))
      (node (ref "U1") (pin "GND") (pinfunction "GND_GND") (pintype "bidirectional"))
      (node (ref "U2") (pin "4") (pinfunction "GND_4") (pintype "bidirectional"))
    )
    (net (code "10") (name "HV_HA_0") (class "Default")
      (node (ref "SV1") (pin "10") (pinfunction "10_10") (pintype "passive"))
      (node (ref "U$1") (pin "35") (pinfunction "HV1_35") (pintype "bidirectional"))
    )
    (net (code "11") (name "HV_HA_1") (class "Default")
      (node (ref "SV1") (pin "9") (pinfunction "9_9") (pintype "passive"))
      (node (ref "U$1") (pin "40") (pinfunction "HV6_40") (pintype "bidirectional"))
    )
    (net (code "12") (name "HV_HA_2") (class "Default")
      (node (ref "SV1") (pin "7") (pinfunction "7_7") (pintype "passive"))
      (node (ref "U$1") (pin "41") (pinfunction "HV7_41") (pintype "bidirectional"))
    )
    (net (code "13") (name "HV_HA_3") (class "Default")
      (node (ref "SV1") (pin "5") (pinfunction "5_5") (pintype "passive"))
      (node (ref "U$1") (pin "42") (pinfunction "HV8_42") (pintype "bidirectional"))
    )
    (net (code "14") (name "HV_HA_4") (class "Default")
      (node (ref "SV1") (pin "3") (pinfunction "3_3") (pintype "passive"))
      (node (ref "U$1") (pin "43") (pinfunction "HV9_43") (pintype "bidirectional"))
    )
    (net (code "15") (name "HV_HA_5") (class "Default")
      (node (ref "SV1") (pin "1") (pinfunction "1_1") (pintype "passive"))
      (node (ref "U$1") (pin "44") (pinfunction "HV10_44") (pintype "bidirectional"))
    )
    (net (code "16") (name "HV_HA_6") (class "Default")
      (node (ref "SV1") (pin "2") (pinfunction "2_2") (pintype "passive"))
      (node (ref "U$1") (pin "39") (pinfunction "HV5_39") (pintype "bidirectional"))
    )
    (net (code "17") (name "HV_HA_7") (class "Default")
      (node (ref "SV1") (pin "4") (pinfunction "4_4") (pintype "passive"))
      (node (ref "U$1") (pin "38") (pinfunction "HV4_38") (pintype "bidirectional"))
    )
    (net (code "18") (name "HV_HA_8") (class "Default")
      (node (ref "SV1") (pin "6") (pinfunction "6_6") (pintype "passive"))
      (node (ref "U$1") (pin "37") (pinfunction "HV3_37") (pintype "bidirectional"))
    )
    (net (code "19") (name "HV_HA_9") (class "Default")
      (node (ref "SV1") (pin "8") (pinfunction "8_8") (pintype "passive"))
      (node (ref "U$1") (pin "36") (pinfunction "HV2_36") (pintype "bidirectional"))
    )
    (net (code "20") (name "HV_HA_DP") (class "Default")
      (node (ref "R31") (pin "2") (pinfunction "2_2") (pintype "passive"))
      (node (ref "U$1") (pin "1") (pinfunction "HV11_1") (pintype "bidirectional"))
    )
    (net (code "21") (name "HV_HB_0") (class "Default")
      (node (ref "SV2") (pin "10") (pinfunction "10_10") (pintype "passive"))
      (node (ref "U$1") (pin "8") (pinfunction "HV18_8") (pintype "bidirectional"))
    )
    (net (code "22") (name "HV_HB_1") (class "Default")
      (node (ref "SV2") (pin "9") (pinfunction "9_9") (pintype "passive"))
      (node (ref "U$1") (pin "6") (pinfunction "HV16_6") (pintype "bidirectional"))
    )
    (net (code "23") (name "HV_HB_2") (class "Default")
      (node (ref "SV2") (pin "7") (pinfunction "7_7") (pintype "passive"))
      (node (ref "U$1") (pin "5") (pinfunction "HV15_5") (pintype "bidirectional"))
    )
    (net (code "24") (name "HV_HB_3") (class "Default")
      (node (ref "SV2") (pin "5") (pinfunction "5_5") (pintype "passive"))
      (node (ref "U$1") (pin "4") (pinfunction "HV14_4") (pintype "bidirectional"))
    )
    (net (code "25") (name "HV_HB_4") (class "Default")
      (node (ref "SV2") (pin "3") (pinfunction "3_3") (pintype "passive"))
      (node (ref "U$1") (pin "3") (pinfunction "HV13_3") (pintype "bidirectional"))
    )
    (net (code "26") (name "HV_HB_5") (class "Default")
      (node (ref "SV2") (pin "1") (pinfunction "1_1") (pintype "passive"))
      (node (ref "U$1") (pin "2") (pinfunction "HV12_2") (pintype "bidirectional"))
    )
    (net (code "27") (name "HV_HB_6") (class "Default")
      (node (ref "SV2") (pin "2") (pinfunction "2_2") (pintype "passive"))
      (node (ref "U$1") (pin "12") (pinfunction "HV22_12") (pintype "bidirectional"))
    )
    (net (code "28") (name "HV_HB_7") (class "Default")
      (node (ref "SV2") (pin "4") (pinfunction "4_4") (pintype "passive"))
      (node (ref "U$1") (pin "11") (pinfunction "HV21_11") (pintype "bidirectional"))
    )
    (net (code "29") (name "HV_HB_8") (class "Default")
      (node (ref "SV2") (pin "6") (pinfunction "6_6") (pintype "passive"))
      (node (ref "U$1") (pin "10") (pinfunction "HV20_10") (pintype "bidirectional"))
    )
    (net (code "30") (name "HV_HB_9") (class "Default")
      (node (ref "SV2") (pin "8") (pinfunction "8_8") (pintype "passive"))
      (node (ref "U$1") (pin "9") (pinfunction "HV19_9") (pintype "bidirectional"))
    )
    (net (code "31") (name "HV_HB_DP") (class "Default")
      (node (ref "R33") (pin "2") (pinfunction "2_2") (pintype "passive"))
      (node (ref "U$1") (pin "7") (pinfunction "HV17_7") (pintype "bidirectional"))
    )
    (net (code "32") (name "HV_IN+") (class "Default")
      (node (ref "C13") (pin "+") (pinfunction "+_+") (pintype "passive"))
      (node (ref "D2") (pin "3") (pinfunction "C_3") (pintype "passive"))
      (node (ref "R15") (pin "2") (pinfunction "2_2") (pintype "passive"))
      (node (ref "R16") (pin "2") (pinfunction "2_2") (pintype "passive"))
      (node (ref "R17") (pin "2") (pinfunction "2_2") (pintype "passive"))
      (node (ref "R18") (pin "2") (pinfunction "2_2") (pintype "passive"))
      (node (ref "R19") (pin "2") (pinfunction "2_2") (pintype "passive"))
      (node (ref "R20") (pin "2") (pinfunction "2_2") (pintype "passive"))
      (node (ref "R24") (pin "1") (pinfunction "1_1") (pintype "passive"))
    )
    (net (code "33") (name "HV_MA_0") (class "Default")
      (node (ref "SV3") (pin "10") (pinfunction "10_10") (pintype "passive"))
      (node (ref "U$1") (pin "17") (pinfunction "HV27_17") (pintype "bidirectional"))
    )
    (net (code "34") (name "HV_MA_1") (class "Default")
      (node (ref "SV3") (pin "9") (pinfunction "9_9") (pintype "passive"))
      (node (ref "U$1") (pin "18") (pinfunction "HV28_18") (pintype "bidirectional"))
    )
    (net (code "35") (name "HV_MA_2") (class "Default")
      (node (ref "SV3") (pin "7") (pinfunction "7_7") (pintype "passive"))
      (node (ref "U$1") (pin "19") (pinfunction "HV29_19") (pintype "bidirectional"))
    )
    (net (code "36") (name "HV_MA_3") (class "Default")
      (node (ref "SV3") (pin "5") (pinfunction "5_5") (pintype "passive"))
      (node (ref "U$1") (pin "20") (pinfunction "HV30_20") (pintype "bidirectional"))
    )
    (net (code "37") (name "HV_MA_4") (class "Default")
      (node (ref "SV3") (pin "3") (pinfunction "3_3") (pintype "passive"))
      (node (ref "U$1") (pin "21") (pinfunction "HV31_21") (pintype "bidirectional"))
    )
    (net (code "38") (name "HV_MA_5") (class "Default")
      (node (ref "SV3") (pin "1") (pinfunction "1_1") (pintype "passive"))
      (node (ref "U$1") (pin "22") (pinfunction "HV32_22") (pintype "bidirectional"))
    )
    (net (code "39") (name "HV_MA_6") (class "Default")
      (node (ref "SV3") (pin "2") (pinfunction "2_2") (pintype "passive"))
      (node (ref "U$1") (pin "13") (pinfunction "HV23_13") (pintype "bidirectional"))
    )
    (net (code "40") (name "HV_MA_7") (class "Default")
      (node (ref "SV3") (pin "4") (pinfunction "4_4") (pintype "passive"))
      (node (ref "U$1") (pin "14") (pinfunction "HV24_14") (pintype "bidirectional"))
    )
    (net (code "41") (name "HV_MA_8") (class "Default")
      (node (ref "SV3") (pin "6") (pinfunction "6_6") (pintype "passive"))
      (node (ref "U$1") (pin "15") (pinfunction "HV25_15") (pintype "bidirectional"))
    )
    (net (code "42") (name "HV_MA_9") (class "Default")
      (node (ref "SV3") (pin "8") (pinfunction "8_8") (pintype "passive"))
      (node (ref "U$1") (pin "16") (pinfunction "HV26_16") (pintype "bidirectional"))
    )
    (net (code "43") (name "HV_MA_DP") (class "Default")
      (node (ref "R34") (pin "2") (pinfunction "2_2") (pintype "passive"))
      (node (ref "U$2") (pin "2") (pinfunction "HV12_2") (pintype "bidirectional"))
    )
    (net (code "44") (name "HV_MB_0") (class "Default")
      (node (ref "SV4") (pin "10") (pinfunction "10_10") (pintype "passive"))
      (node (ref "U$2") (pin "39") (pinfunction "HV5_39") (pintype "bidirectional"))
    )
    (net (code "45") (name "HV_MB_1") (class "Default")
      (node (ref "SV4") (pin "9") (pinfunction "9_9") (pintype "passive"))
      (node (ref "U$2") (pin "41") (pinfunction "HV7_41") (pintype "bidirectional"))
    )
    (net (code "46") (name "HV_MB_2") (class "Default")
      (node (ref "SV4") (pin "7") (pinfunction "7_7") (pintype "passive"))
      (node (ref "U$2") (pin "42") (pinfunction "HV8_42") (pintype "bidirectional"))
    )
    (net (code "47") (name "HV_MB_3") (class "Default")
      (node (ref "SV4") (pin "5") (pinfunction "5_5") (pintype "passive"))
      (node (ref "U$2") (pin "43") (pinfunction "HV9_43") (pintype "bidirectional"))
    )
    (net (code "48") (name "HV_MB_4") (class "Default")
      (node (ref "SV4") (pin "3") (pinfunction "3_3") (pintype "passive"))
      (node (ref "U$2") (pin "44") (pinfunction "HV10_44") (pintype "bidirectional"))
    )
    (net (code "49") (name "HV_MB_5") (class "Default")
      (node (ref "SV4") (pin "1") (pinfunction "1_1") (pintype "passive"))
      (node (ref "U$2") (pin "1") (pinfunction "HV11_1") (pintype "bidirectional"))
    )
    (net (code "50") (name "HV_MB_6") (class "Default")
      (node (ref "SV4") (pin "2") (pinfunction "2_2") (pintype "passive"))
      (node (ref "U$2") (pin "35") (pinfunction "HV1_35") (pintype "bidirectional"))
    )
    (net (code "51") (name "HV_MB_7") (class "Default")
      (node (ref "SV4") (pin "4") (pinfunction "4_4") (pintype "passive"))
      (node (ref "U$2") (pin "36") (pinfunction "HV2_36") (pintype "bidirectional"))
    )
    (net (code "52") (name "HV_MB_8") (class "Default")
      (node (ref "SV4") (pin "6") (pinfunction "6_6") (pintype "passive"))
      (node (ref "U$2") (pin "37") (pinfunction "HV3_37") (pintype "bidirectional"))
    )
    (net (code "53") (name "HV_MB_9") (class "Default")
      (node (ref "SV4") (pin "8") (pinfunction "8_8") (pintype "passive"))
      (node (ref "U$2") (pin "38") (pinfunction "HV4_38") (pintype "bidirectional"))
    )
    (net (code "54") (name "HV_MB_DP") (class "Default")
      (node (ref "R35") (pin "2") (pinfunction "2_2") (pintype "passive"))
      (node (ref "U$2") (pin "40") (pinfunction "HV6_40") (pintype "bidirectional"))
    )
    (net (code "55") (name "HV_SA_0") (class "Default")
      (node (ref "SV5") (pin "10") (pinfunction "10_10") (pintype "passive"))
      (node (ref "U$2") (pin "8") (pinfunction "HV18_8") (pintype "bidirectional"))
    )
    (net (code "56") (name "HV_SA_1") (class "Default")
      (node (ref "SV5") (pin "9") (pinfunction "9_9") (pintype "passive"))
      (node (ref "U$2") (pin "7") (pinfunction "HV17_7") (pintype "bidirectional"))
    )
    (net (code "57") (name "HV_SA_2") (class "Default")
      (node (ref "SV5") (pin "7") (pinfunction "7_7") (pintype "passive"))
      (node (ref "U$2") (pin "6") (pinfunction "HV16_6") (pintype "bidirectional"))
    )
    (net (code "58") (name "HV_SA_3") (class "Default")
      (node (ref "SV5") (pin "5") (pinfunction "5_5") (pintype "passive"))
      (node (ref "U$2") (pin "5") (pinfunction "HV15_5") (pintype "bidirectional"))
    )
    (net (code "59") (name "HV_SA_4") (class "Default")
      (node (ref "SV5") (pin "3") (pinfunction "3_3") (pintype "passive"))
      (node (ref "U$2") (pin "4") (pinfunction "HV14_4") (pintype "bidirectional"))
    )
    (net (code "60") (name "HV_SA_5") (class "Default")
      (node (ref "SV5") (pin "1") (pinfunction "1_1") (pintype "passive"))
      (node (ref "U$2") (pin "3") (pinfunction "HV13_3") (pintype "bidirectional"))
    )
    (net (code "61") (name "HV_SA_6") (class "Default")
      (node (ref "SV5") (pin "2") (pinfunction "2_2") (pintype "passive"))
      (node (ref "U$2") (pin "12") (pinfunction "HV22_12") (pintype "bidirectional"))
    )
    (net (code "62") (name "HV_SA_7") (class "Default")
      (node (ref "SV5") (pin "4") (pinfunction "4_4") (pintype "passive"))
      (node (ref "U$2") (pin "11") (pinfunction "HV21_11") (pintype "bidirectional"))
    )
    (net (code "63") (name "HV_SA_8") (class "Default")
      (node (ref "SV5") (pin "6") (pinfunction "6_6") (pintype "passive"))
      (node (ref "U$2") (pin "10") (pinfunction "HV20_10") (pintype "bidirectional"))
    )
    (net (code "64") (name "HV_SA_9") (class "Default")
      (node (ref "SV5") (pin "8") (pinfunction "8_8") (pintype "passive"))
      (node (ref "U$2") (pin "9") (pinfunction "HV19_9") (pintype "bidirectional"))
    )
    (net (code "65") (name "HV_SB_0") (class "Default")
      (node (ref "SV6") (pin "10") (pinfunction "10_10") (pintype "passive"))
      (node (ref "U$2") (pin "17") (pinfunction "HV27_17") (pintype "bidirectional"))
    )
    (net (code "66") (name "HV_SB_1") (class "Default")
      (node (ref "SV6") (pin "9") (pinfunction "9_9") (pintype "passive"))
      (node (ref "U$2") (pin "22") (pinfunction "HV32_22") (pintype "bidirectional"))
    )
    (net (code "67") (name "HV_SB_2") (class "Default")
      (node (ref "SV6") (pin "7") (pinfunction "7_7") (pintype "passive"))
      (node (ref "U$2") (pin "21") (pinfunction "HV31_21") (pintype "bidirectional"))
    )
    (net (code "68") (name "HV_SB_3") (class "Default")
      (node (ref "SV6") (pin "5") (pinfunction "5_5") (pintype "passive"))
      (node (ref "U$2") (pin "20") (pinfunction "HV30_20") (pintype "bidirectional"))
    )
    (net (code "69") (name "HV_SB_4") (class "Default")
      (node (ref "SV6") (pin "3") (pinfunction "3_3") (pintype "passive"))
      (node (ref "U$2") (pin "19") (pinfunction "HV29_19") (pintype "bidirectional"))
    )
    (net (code "70") (name "HV_SB_5") (class "Default")
      (node (ref "SV6") (pin "1") (pinfunction "1_1") (pintype "passive"))
      (node (ref "U$2") (pin "18") (pinfunction "HV28_18") (pintype "bidirectional"))
    )
    (net (code "71") (name "HV_SB_6") (class "Default")
      (node (ref "SV6") (pin "2") (pinfunction "2_2") (pintype "passive"))
      (node (ref "U$2") (pin "13") (pinfunction "HV23_13") (pintype "bidirectional"))
    )
    (net (code "72") (name "HV_SB_7") (class "Default")
      (node (ref "SV6") (pin "4") (pinfunction "4_4") (pintype "passive"))
      (node (ref "U$2") (pin "14") (pinfunction "HV24_14") (pintype "bidirectional"))
    )
    (net (code "73") (name "HV_SB_8") (class "Default")
      (node (ref "SV6") (pin "6") (pinfunction "6_6") (pintype "passive"))
      (node (ref "U$2") (pin "15") (pinfunction "HV25_15") (pintype "bidirectional"))
    )
    (net (code "74") (name "HV_SB_9") (class "Default")
      (node (ref "SV6") (pin "8") (pinfunction "8_8") (pintype "passive"))
      (node (ref "U$2") (pin "16") (pinfunction "HV26_16") (pintype "bidirectional"))
    )
    (net (code "75") (name "LE") (class "Default")
      (node (ref "R2") (pin "1") (pinfunction "1_1") (pintype "passive"))
      (node (ref "U1") (pin "GPIO4") (pinfunction "GPIO4_GPIO4") (pintype "bidirectional"))
    )
    (net (code "76") (name "Net-(D4-PadA)") (class "Default")
      (node (ref "D4") (pin "A") (pinfunction "A_A") (pintype "passive"))
      (node (ref "J5") (pin "3") (pinfunction "3_3") (pintype "passive"))
    )
    (net (code "77") (name "Net-(L1-1)") (class "Default")
      (node (ref "D3") (pin "C") (pinfunction "C_C") (pintype "passive"))
      (node (ref "L1") (pin "P$1") (pinfunction "1_P$1") (pintype "passive"))
      (node (ref "U$5") (pin "2") (pinfunction "ES_2") (pintype "bidirectional"))
    )
    (net (code "78") (name "Net-(L3-1)") (class "Default")
      (node (ref "C12") (pin "+") (pinfunction "+_+") (pintype "passive"))
      (node (ref "L3") (pin "P$1") (pinfunction "1_P$1") (pintype "passive"))
      (node (ref "R22") (pin "2") (pinfunction "2_2") (pintype "passive"))
      (node (ref "R23") (pin "2") (pinfunction "2_2") (pintype "passive"))
      (node (ref "U$18") (pin "1") (pinfunction "CS_1") (pintype "bidirectional"))
      (node (ref "U$18") (pin "7") (pinfunction "IS_7") (pintype "bidirectional"))
      (node (ref "U$18") (pin "8") (pinfunction "CD_8") (pintype "bidirectional"))
    )
    (net (code "79") (name "Net-(N1-Pad0)") (class "Default")
      (node (ref "N1") (pin "0") (pinfunction "0_0") (pintype "bidirectional"))
      (node (ref "SV7") (pin "10") (pinfunction "10_10") (pintype "passive"))
    )
    (net (code "80") (name "Net-(N1-Pad1)") (class "Default")
      (node (ref "N1") (pin "1") (pinfunction "1_1") (pintype "bidirectional"))
      (node (ref "SV7") (pin "9") (pinfunction "9_9") (pintype "passive"))
    )
    (net (code "81") (name "Net-(N1-Pad2)") (class "Default")
      (node (ref "N1") (pin "2") (pinfunction "2_2") (pintype "bidirectional"))
      (node (ref "SV7") (pin "7") (pinfunction "7_7") (pintype "passive"))
    )
    (net (code "82") (name "Net-(N1-Pad3)") (class "Default")
      (node (ref "N1") (pin "3") (pinfunction "3_3") (pintype "bidirectional"))
      (node (ref "SV7") (pin "5") (pinfunction "5_5") (pintype "passive"))
    )
    (net (code "83") (name "Net-(N1-Pad4)") (class "Default")
      (node (ref "N1") (pin "4") (pinfunction "4_4") (pintype "bidirectional"))
      (node (ref "SV7") (pin "3") (pinfunction "3_3") (pintype "passive"))
    )
    (net (code "84") (name "Net-(N1-Pad5)") (class "Default")
      (node (ref "N1") (pin "5") (pinfunction "5_5") (pintype "bidirectional"))
      (node (ref "SV7") (pin "1") (pinfunction "1_1") (pintype "passive"))
    )
    (net (code "85") (name "Net-(N1-Pad6)") (class "Default")
      (node (ref "N1") (pin "6") (pinfunction "6_6") (pintype "bidirectional"))
      (node (ref "SV7") (pin "2") (pinfunction "2_2") (pintype "passive"))
    )
    (net (code "86") (name "Net-(N1-Pad7)") (class "Default")
      (node (ref "N1") (pin "7") (pinfunction "7_7") (pintype "bidirectional"))
      (node (ref "SV7") (pin "4") (pinfunction "4_4") (pintype "passive"))
    )
    (net (code "87") (name "Net-(N1-Pad8)") (class "Default")
      (node (ref "N1") (pin "8") (pinfunction "8_8") (pintype "bidirectional"))
      (node (ref "SV7") (pin "6") (pinfunction "6_6") (pintype "passive"))
    )
    (net (code "88") (name "Net-(N1-Pad9)") (class "Default")
      (node (ref "N1") (pin "9") (pinfunction "9_9") (pintype "bidirectional"))
      (node (ref "SV7") (pin "8") (pinfunction "8_8") (pintype "passive"))
    )
    (net (code "89") (name "Net-(N1-PadA)") (class "Default")
      (node (ref "N1") (pin "A") (pinfunction "A_A") (pintype "bidirectional"))
      (node (ref "SV7") (pin "12") (pinfunction "12_12") (pintype "passive"))
    )
    (net (code "90") (name "Net-(N1-PadRHDP)") (class "Default")
      (node (ref "N1") (pin "RHDP") (pinfunction "RHDP_RHDP") (pintype "bidirectional"))
      (node (ref "SV7") (pin "11") (pinfunction "11_11") (pintype "passive"))
    )
    (net (code "91") (name "Net-(N2-Pad0)") (class "Default")
      (node (ref "N2") (pin "0") (pinfunction "0_0") (pintype "bidirectional"))
      (node (ref "SV8") (pin "10") (pinfunction "10_10") (pintype "passive"))
    )
    (net (code "92") (name "Net-(N2-Pad1)") (class "Default")
      (node (ref "N2") (pin "1") (pinfunction "1_1") (pintype "bidirectional"))
      (node (ref "SV8") (pin "9") (pinfunction "9_9") (pintype "passive"))
    )
    (net (code "93") (name "Net-(N2-Pad2)") (class "Default")
      (node (ref "N2") (pin "2") (pinfunction "2_2") (pintype "bidirectional"))
      (node (ref "SV8") (pin "7") (pinfunction "7_7") (pintype "passive"))
    )
    (net (code "94") (name "Net-(N2-Pad3)") (class "Default")
      (node (ref "N2") (pin "3") (pinfunction "3_3") (pintype "bidirectional"))
      (node (ref "SV8") (pin "5") (pinfunction "5_5") (pintype "passive"))
    )
    (net (code "95") (name "Net-(N2-Pad4)") (class "Default")
      (node (ref "N2") (pin "4") (pinfunction "4_4") (pintype "bidirectional"))
      (node (ref "SV8") (pin "3") (pinfunction "3_3") (pintype "passive"))
    )
    (net (code "96") (name "Net-(N2-Pad5)") (class "Default")
      (node (ref "N2") (pin "5") (pinfunction "5_5") (pintype "bidirectional"))
      (node (ref "SV8") (pin "1") (pinfunction "1_1") (pintype "passive"))
    )
    (net (code "97") (name "Net-(N2-Pad6)") (class "Default")
      (node (ref "N2") (pin "6") (pinfunction "6_6") (pintype "bidirectional"))
      (node (ref "SV8") (pin "2") (pinfunction "2_2") (pintype "passive"))
    )
    (net (code "98") (name "Net-(N2-Pad7)") (class "Default")
      (node (ref "N2") (pin "7") (pinfunction "7_7") (pintype "bidirectional"))
      (node (ref "SV8") (pin "4") (pinfunction "4_4") (pintype "passive"))
    )
    (net (code "99") (name "Net-(N2-Pad8)") (class "Default")
      (node (ref "N2") (pin "8") (pinfunction "8_8") (pintype "bidirectional"))
      (node (ref "SV8") (pin "6") (pinfunction "6_6") (pintype "passive"))
    )
    (net (code "100") (name "Net-(N2-Pad9)") (class "Default")
      (node (ref "N2") (pin "9") (pinfunction "9_9") (pintype "bidirectional"))
      (node (ref "SV8") (pin "8") (pinfunction "8_8") (pintype "passive"))
    )
    (net (code "101") (name "Net-(N2-PadA)") (class "Default")
      (node (ref "N2") (pin "A") (pinfunction "A_A") (pintype "bidirectional"))
      (node (ref "SV8") (pin "12") (pinfunction "12_12") (pintype "passive"))
    )
    (net (code "102") (name "Net-(N2-PadRHDP)") (class "Default")
      (node (ref "N2") (pin "RHDP") (pinfunction "RHDP_RHDP") (pintype "bidirectional"))
      (node (ref "SV8") (pin "11") (pinfunction "11_11") (pintype "passive"))
    )
    (net (code "103") (name "Net-(N3-Pad0)") (class "Default")
      (node (ref "N3") (pin "0") (pinfunction "0_0") (pintype "bidirectional"))
      (node (ref "SV9") (pin "10") (pinfunction "10_10") (pintype "passive"))
    )
    (net (code "104") (name "Net-(N3-Pad1)") (class "Default")
      (node (ref "N3") (pin "1") (pinfunction "1_1") (pintype "bidirectional"))
      (node (ref "SV9") (pin "9") (pinfunction "9_9") (pintype "passive"))
    )
    (net (code "105") (name "Net-(N3-Pad2)") (class "Default")
      (node (ref "N3") (pin "2") (pinfunction "2_2") (pintype "bidirectional"))
      (node (ref "SV9") (pin "7") (pinfunction "7_7") (pintype "passive"))
    )
    (net (code "106") (name "Net-(N3-Pad3)") (class "Default")
      (node (ref "N3") (pin "3") (pinfunction "3_3") (pintype "bidirectional"))
      (node (ref "SV9") (pin "5") (pinfunction "5_5") (pintype "passive"))
    )
    (net (code "107") (name "Net-(N3-Pad4)") (class "Default")
      (node (ref "N3") (pin "4") (pinfunction "4_4") (pintype "bidirectional"))
      (node (ref "SV9") (pin "3") (pinfunction "3_3") (pintype "passive"))
    )
    (net (code "108") (name "Net-(N3-Pad5)") (class "Default")
      (node (ref "N3") (pin "5") (pinfunction "5_5") (pintype "bidirectional"))
      (node (ref "SV9") (pin "1") (pinfunction "1_1") (pintype "passive"))
    )
    (net (code "109") (name "Net-(N3-Pad6)") (class "Default")
      (node (ref "N3") (pin "6") (pinfunction "6_6") (pintype "bidirectional"))
      (node (ref "SV9") (pin "2") (pinfunction "2_2") (pintype "passive"))
    )
    (net (code "110") (name "Net-(N3-Pad7)") (class "Default")
      (node (ref "N3") (pin "7") (pinfunction "7_7") (pintype "bidirectional"))
      (node (ref "SV9") (pin "4") (pinfunction "4_4") (pintype "passive"))
    )
    (net (code "111") (name "Net-(N3-Pad8)") (class "Default")
      (node (ref "N3") (pin "8") (pinfunction "8_8") (pintype "bidirectional"))
      (node (ref "SV9") (pin "6") (pinfunction "6_6") (pintype "passive"))
    )
    (net (code "112") (name "Net-(N3-Pad9)") (class "Default")
      (node (ref "N3") (pin "9") (pinfunction "9_9") (pintype "bidirectional"))
      (node (ref "SV9") (pin "8") (pinfunction "8_8") (pintype "passive"))
    )
    (net (code "113") (name "Net-(N3-PadA)") (class "Default")
      (node (ref "N3") (pin "A") (pinfunction "A_A") (pintype "bidirectional"))
      (node (ref "SV9") (pin "12") (pinfunction "12_12") (pintype "passive"))
    )
    (net (code "114") (name "Net-(N3-PadRHDP)") (class "Default")
      (node (ref "N3") (pin "RHDP") (pinfunction "RHDP_RHDP") (pintype "bidirectional"))
      (node (ref "SV9") (pin "11") (pinfunction "11_11") (pintype "passive"))
    )
    (net (code "115") (name "Net-(N4-Pad0)") (class "Default")
      (node (ref "N4") (pin "0") (pinfunction "0_0") (pintype "bidirectional"))
      (node (ref "SV10") (pin "10") (pinfunction "10_10") (pintype "passive"))
    )
    (net (code "116") (name "Net-(N4-Pad1)") (class "Default")
      (node (ref "N4") (pin "1") (pinfunction "1_1") (pintype "bidirectional"))
      (node (ref "SV10") (pin "9") (pinfunction "9_9") (pintype "passive"))
    )
    (net (code "117") (name "Net-(N4-Pad2)") (class "Default")
      (node (ref "N4") (pin "2") (pinfunction "2_2") (pintype "bidirectional"))
      (node (ref "SV10") (pin "7") (pinfunction "7_7") (pintype "passive"))
    )
    (net (code "118") (name "Net-(N4-Pad3)") (class "Default")
      (node (ref "N4") (pin "3") (pinfunction "3_3") (pintype "bidirectional"))
      (node (ref "SV10") (pin "5") (pinfunction "5_5") (pintype "passive"))
    )
    (net (code "119") (name "Net-(N4-Pad4)") (class "Default")
      (node (ref "N4") (pin "4") (pinfunction "4_4") (pintype "bidirectional"))
      (node (ref "SV10") (pin "3") (pinfunction "3_3") (pintype "passive"))
    )
    (net (code "120") (name "Net-(N4-Pad5)") (class "Default")
      (node (ref "N4") (pin "5") (pinfunction "5_5") (pintype "bidirectional"))
      (node (ref "SV10") (pin "1") (pinfunction "1_1") (pintype "passive"))
    )
    (net (code "121") (name "Net-(N4-Pad6)") (class "Default")
      (node (ref "N4") (pin "6") (pinfunction "6_6") (pintype "bidirectional"))
      (node (ref "SV10") (pin "2") (pinfunction "2_2") (pintype "passive"))
    )
    (net (code "122") (name "Net-(N4-Pad7)") (class "Default")
      (node (ref "N4") (pin "7") (pinfunction "7_7") (pintype "bidirectional"))
      (node (ref "SV10") (pin "4") (pinfunction "4_4") (pintype "passive"))
    )
    (net (code "123") (name "Net-(N4-Pad8)") (class "Default")
      (node (ref "N4") (pin "8") (pinfunction "8_8") (pintype "bidirectional"))
      (node (ref "SV10") (pin "6") (pinfunction "6_6") (pintype "passive"))
    )
    (net (code "124") (name "Net-(N4-Pad9)") (class "Default")
      (node (ref "N4") (pin "9") (pinfunction "9_9") (pintype "bidirectional"))
      (node (ref "SV10") (pin "8") (pinfunction "8_8") (pintype "passive"))
    )
    (net (code "125") (name "Net-(N4-PadA)") (class "Default")
      (node (ref "N4") (pin "A") (pinfunction "A_A") (pintype "bidirectional"))
      (node (ref "SV10") (pin "12") (pinfunction "12_12") (pintype "passive"))
    )
    (net (code "126") (name "Net-(N4-PadRHDP)") (class "Default")
      (node (ref "N4") (pin "RHDP") (pinfunction "RHDP_RHDP") (pintype "bidirectional"))
      (node (ref "SV10") (pin "11") (pinfunction "11_11") (pintype "passive"))
    )
    (net (code "127") (name "Net-(N5-Pad0)") (class "Default")
      (node (ref "N5") (pin "0") (pinfunction "0_0") (pintype "bidirectional"))
      (node (ref "SV11") (pin "10") (pinfunction "10_10") (pintype "passive"))
    )
    (net (code "128") (name "Net-(N5-Pad1)") (class "Default")
      (node (ref "N5") (pin "1") (pinfunction "1_1") (pintype "bidirectional"))
      (node (ref "SV11") (pin "9") (pinfunction "9_9") (pintype "passive"))
    )
    (net (code "129") (name "Net-(N5-Pad2)") (class "Default")
      (node (ref "N5") (pin "2") (pinfunction "2_2") (pintype "bidirectional"))
      (node (ref "SV11") (pin "7") (pinfunction "7_7") (pintype "passive"))
    )
    (net (code "130") (name "Net-(N5-Pad3)") (class "Default")
      (node (ref "N5") (pin "3") (pinfunction "3_3") (pintype "bidirectional"))
      (node (ref "SV11") (pin "5") (pinfunction "5_5") (pintype "passive"))
    )
    (net (code "131") (name "Net-(N5-Pad4)") (class "Default")
      (node (ref "N5") (pin "4") (pinfunction "4_4") (pintype "bidirectional"))
      (node (ref "SV11") (pin "3") (pinfunction "3_3") (pintype "passive"))
    )
    (net (code "132") (name "Net-(N5-Pad5)") (class "Default")
      (node (ref "N5") (pin "5") (pinfunction "5_5") (pintype "bidirectional"))
      (node (ref "SV11") (pin "1") (pinfunction "1_1") (pintype "passive"))
    )
    (net (code "133") (name "Net-(N5-Pad6)") (class "Default")
      (node (ref "N5") (pin "6") (pinfunction "6_6") (pintype "bidirectional"))
      (node (ref "SV11") (pin "2") (pinfunction "2_2") (pintype "passive"))
    )
    (net (code "134") (name "Net-(N5-Pad7)") (class "Default")
      (node (ref "N5") (pin "7") (pinfunction "7_7") (pintype "bidirectional"))
      (node (ref "SV11") (pin "4") (pinfunction "4_4") (pintype "passive"))
    )
    (net (code "135") (name "Net-(N5-Pad8)") (class "Default")
      (node (ref "N5") (pin "8") (pinfunction "8_8") (pintype "bidirectional"))
      (node (ref "SV11") (pin "6") (pinfunction "6_6") (pintype "passive"))
    )
    (net (code "136") (name "Net-(N5-Pad9)") (class "Default")
      (node (ref "N5") (pin "9") (pinfunction "9_9") (pintype "bidirectional"))
      (node (ref "SV11") (pin "8") (pinfunction "8_8") (pintype "passive"))
    )
    (net (code "137") (name "Net-(N5-PadA)") (class "Default")
      (node (ref "N5") (pin "A") (pinfunction "A_A") (pintype "bidirectional"))
      (node (ref "SV11") (pin "12") (pinfunction "12_12") (pintype "passive"))
    )
    (net (code "138") (name "Net-(N5-PadRHDP)") (class "Default")
      (node (ref "N5") (pin "RHDP") (pinfunction "RHDP_RHDP") (pintype "bidirectional"))
      (node (ref "SV11") (pin "11") (pinfunction "11_11") (pintype "passive"))
    )
    (net (code "139") (name "Net-(N6-Pad0)") (class "Default")
      (node (ref "N6") (pin "0") (pinfunction "0_0") (pintype "bidirectional"))
      (node (ref "SV12") (pin "10") (pinfunction "10_10") (pintype "passive"))
    )
    (net (code "140") (name "Net-(N6-Pad1)") (class "Default")
      (node (ref "N6") (pin "1") (pinfunction "1_1") (pintype "bidirectional"))
      (node (ref "SV12") (pin "9") (pinfunction "9_9") (pintype "passive"))
    )
    (net (code "141") (name "Net-(N6-Pad2)") (class "Default")
      (node (ref "N6") (pin "2") (pinfunction "2_2") (pintype "bidirectional"))
      (node (ref "SV12") (pin "7") (pinfunction "7_7") (pintype "passive"))
    )
    (net (code "142") (name "Net-(N6-Pad3)") (class "Default")
      (node (ref "N6") (pin "3") (pinfunction "3_3") (pintype "bidirectional"))
      (node (ref "SV12") (pin "5") (pinfunction "5_5") (pintype "passive"))
    )
    (net (code "143") (name "Net-(N6-Pad4)") (class "Default")
      (node (ref "N6") (pin "4") (pinfunction "4_4") (pintype "bidirectional"))
      (node (ref "SV12") (pin "3") (pinfunction "3_3") (pintype "passive"))
    )
    (net (code "144") (name "Net-(N6-Pad5)") (class "Default")
      (node (ref "N6") (pin "5") (pinfunction "5_5") (pintype "bidirectional"))
      (node (ref "SV12") (pin "1") (pinfunction "1_1") (pintype "passive"))
    )
    (net (code "145") (name "Net-(N6-Pad6)") (class "Default")
      (node (ref "N6") (pin "6") (pinfunction "6_6") (pintype "bidirectional"))
      (node (ref "SV12") (pin "2") (pinfunction "2_2") (pintype "passive"))
    )
    (net (code "146") (name "Net-(N6-Pad7)") (class "Default")
      (node (ref "N6") (pin "7") (pinfunction "7_7") (pintype "bidirectional"))
      (node (ref "SV12") (pin "4") (pinfunction "4_4") (pintype "passive"))
    )
    (net (code "147") (name "Net-(N6-Pad8)") (class "Default")
      (node (ref "N6") (pin "8") (pinfunction "8_8") (pintype "bidirectional"))
      (node (ref "SV12") (pin "6") (pinfunction "6_6") (pintype "passive"))
    )
    (net (code "148") (name "Net-(N6-Pad9)") (class "Default")
      (node (ref "N6") (pin "9") (pinfunction "9_9") (pintype "bidirectional"))
      (node (ref "SV12") (pin "8") (pinfunction "8_8") (pintype "passive"))
    )
    (net (code "149") (name "Net-(N6-PadA)") (class "Default")
      (node (ref "N6") (pin "A") (pinfunction "A_A") (pintype "bidirectional"))
      (node (ref "SV12") (pin "12") (pinfunction "12_12") (pintype "passive"))
    )
    (net (code "150") (name "Net-(N6-PadRHDP)") (class "Default")
      (node (ref "N6") (pin "RHDP") (pinfunction "RHDP_RHDP") (pintype "bidirectional"))
      (node (ref "SV12") (pin "11") (pinfunction "11_11") (pintype "passive"))
    )
    (net (code "151") (name "Net-(P1-E)") (class "Default")
      (node (ref "P1") (pin "P$3") (pinfunction "E_P$3") (pintype "passive"))
      (node (ref "R26") (pin "2") (pinfunction "2_2") (pintype "passive"))
    )
    (net (code "152") (name "Net-(Q1-B)") (class "Default")
      (node (ref "D1") (pin "A") (pinfunction "A_A") (pintype "passive"))
      (node (ref "Q1") (pin "1") (pinfunction "B_1") (pintype "passive"))
      (node (ref "R21") (pin "1") (pinfunction "1_1") (pintype "passive"))
      (node (ref "U$18") (pin "2") (pinfunction "ES_2") (pintype "bidirectional"))
    )
    (net (code "153") (name "Net-(Q1-E)") (class "Default")
      (node (ref "D1") (pin "C") (pinfunction "C_C") (pintype "passive"))
      (node (ref "Q1") (pin "2") (pinfunction "E_2") (pintype "passive"))
      (node (ref "Q2") (pin "1") (pinfunction "G_1") (pintype "passive"))
    )
    (net (code "154") (name "Net-(R12-Pad1)") (class "Default")
      (node (ref "R12") (pin "1") (pinfunction "1_1") (pintype "passive"))
      (node (ref "U1") (pin "CH_PD") (pinfunction "CH_PD_CH_PD") (pintype "bidirectional"))
    )
    (net (code "155") (name "Net-(R14-Pad2)") (class "Default")
      (node (ref "R14") (pin "2") (pinfunction "2_2") (pintype "passive"))
      (node (ref "U1") (pin "GPIO15") (pinfunction "GPIO15_GPIO15") (pintype "bidirectional"))
    )
    (net (code "156") (name "Net-(R15-Pad1)") (class "Default")
      (node (ref "R15") (pin "1") (pinfunction "1_1") (pintype "passive"))
      (node (ref "SV1") (pin "12") (pinfunction "12_12") (pintype "passive"))
    )
    (net (code "157") (name "Net-(R16-Pad1)") (class "Default")
      (node (ref "R16") (pin "1") (pinfunction "1_1") (pintype "passive"))
      (node (ref "SV2") (pin "12") (pinfunction "12_12") (pintype "passive"))
    )
    (net (code "158") (name "Net-(R17-Pad1)") (class "Default")
      (node (ref "R17") (pin "1") (pinfunction "1_1") (pintype "passive"))
      (node (ref "SV3") (pin "12") (pinfunction "12_12") (pintype "passive"))
    )
    (net (code "159") (name "Net-(R18-Pad1)") (class "Default")
      (node (ref "R18") (pin "1") (pinfunction "1_1") (pintype "passive"))
      (node (ref "SV4") (pin "12") (pinfunction "12_12") (pintype "passive"))
    )
    (net (code "160") (name "Net-(R19-Pad1)") (class "Default")
      (node (ref "R19") (pin "1") (pinfunction "1_1") (pintype "passive"))
      (node (ref "SV5") (pin "12") (pinfunction "12_12") (pintype "passive"))
    )
    (net (code "161") (name "Net-(R20-Pad1)") (class "Default")
      (node (ref "R20") (pin "1") (pinfunction "1_1") (pintype "passive"))
      (node (ref "SV6") (pin "12") (pinfunction "12_12") (pintype "passive"))
    )
    (net (code "162") (name "Net-(R31-Pad1)") (class "Default")
      (node (ref "R31") (pin "1") (pinfunction "1_1") (pintype "passive"))
      (node (ref "SV1") (pin "11") (pinfunction "11_11") (pintype "passive"))
    )
    (net (code "163") (name "Net-(R33-Pad1)") (class "Default")
      (node (ref "R33") (pin "1") (pinfunction "1_1") (pintype "passive"))
      (node (ref "SV2") (pin "11") (pinfunction "11_11") (pintype "passive"))
    )
    (net (code "164") (name "Net-(R34-Pad1)") (class "Default")
      (node (ref "R34") (pin "1") (pinfunction "1_1") (pintype "passive"))
      (node (ref "SV3") (pin "11") (pinfunction "11_11") (pintype "passive"))
    )
    (net (code "165") (name "Net-(R35-Pad1)") (class "Default")
      (node (ref "R35") (pin "1") (pinfunction "1_1") (pintype "passive"))
      (node (ref "SV4") (pin "11") (pinfunction "11_11") (pintype "passive"))
    )
    (net (code "166") (name "Net-(S1-S)") (class "Default")
      (node (ref "R11") (pin "1") (pinfunction "1_1") (pintype "passive"))
      (node (ref "S1") (pin "2") (pinfunction "S_2") (pintype "passive"))
      (node (ref "U1") (pin "RESET") (pinfunction "RESET_RESET") (pintype "bidirectional"))
    )
    (net (code "167") (name "Net-(S2-S)") (class "Default")
      (node (ref "JP1") (pin "1") (pinfunction "1_1") (pintype "passive"))
      (node (ref "R13") (pin "2") (pinfunction "2_2") (pintype "passive"))
      (node (ref "S2") (pin "2") (pinfunction "S_2") (pintype "passive"))
      (node (ref "U1") (pin "GPIO0") (pinfunction "GPIO0_GPIO0") (pintype "bidirectional"))
    )
    (net (code "168") (name "Net-(T1-E)") (class "Default")
      (node (ref "R36") (pin "1") (pinfunction "1_1") (pintype "passive"))
      (node (ref "T1") (pin "EMI") (pinfunction "E_EMI") (pintype "passive"))
    )
    (net (code "169") (name "Net-(U$1-DATA_CLK)") (class "Default")
      (node (ref "R6") (pin "2") (pinfunction "2_2") (pintype "passive"))
      (node (ref "U$1") (pin "28") (pinfunction "DATA_CLK_28") (pintype "bidirectional"))
      (node (ref "U$2") (pin "28") (pinfunction "DATA_CLK_28") (pintype "bidirectional"))
      (node (ref "U$3") (pin "3") (pinfunction "D_3") (pintype "passive"))
    )
    (net (code "170") (name "Net-(U$1-DATA_IN)") (class "Default")
      (node (ref "R3") (pin "2") (pinfunction "2_2") (pintype "passive"))
      (node (ref "U$1") (pin "32") (pinfunction "DATA_IN_32") (pintype "bidirectional"))
      (node (ref "U$3") (pin "6") (pinfunction "D_6") (pintype "passive"))
    )
    (net (code "171") (name "Net-(U$1-DATA_OUT)") (class "Default")
      (node (ref "U$1") (pin "23") (pinfunction "DATA_OUT_23") (pintype "bidirectional"))
      (node (ref "U$2") (pin "32") (pinfunction "DATA_IN_32") (pintype "bidirectional"))
    )
    (net (code "172") (name "Net-(U$1-{slash}LATCH_EN)") (class "Default")
      (node (ref "R1") (pin "2") (pinfunction "2_2") (pintype "passive"))
      (node (ref "U$1") (pin "31") (pinfunction "/LATCH_EN_31") (pintype "bidirectional"))
      (node (ref "U$2") (pin "31") (pinfunction "/LATCH_EN_31") (pintype "bidirectional"))
      (node (ref "U$4") (pin "6") (pinfunction "D_6") (pintype "passive"))
    )
    (net (code "173") (name "Net-(U$3A-G)") (class "Default")
      (node (ref "R4") (pin "2") (pinfunction "2_2") (pintype "passive"))
      (node (ref "U$3") (pin "2") (pinfunction "G_2") (pintype "passive"))
    )
    (net (code "174") (name "Net-(U$3B-G)") (class "Default")
      (node (ref "R5") (pin "2") (pinfunction "2_2") (pintype "passive"))
      (node (ref "U$3") (pin "5") (pinfunction "G_5") (pintype "passive"))
    )
    (net (code "175") (name "Net-(U$4A-G)") (class "Default")
      (node (ref "R2") (pin "2") (pinfunction "2_2") (pintype "passive"))
      (node (ref "U$4") (pin "2") (pinfunction "G_2") (pintype "passive"))
    )
    (net (code "176") (name "Net-(U$5-CD)") (class "Default")
      (node (ref "R9") (pin "2") (pinfunction "2_2") (pintype "passive"))
      (node (ref "U$5") (pin "1") (pinfunction "CS_1") (pintype "bidirectional"))
      (node (ref "U$5") (pin "7") (pinfunction "IS_7") (pintype "bidirectional"))
      (node (ref "U$5") (pin "8") (pinfunction "CD_8") (pintype "bidirectional"))
    )
    (net (code "177") (name "Net-(U$5-CMP)") (class "Default")
      (node (ref "R10") (pin "1") (pinfunction "1_1") (pintype "passive"))
      (node (ref "R32") (pin "2") (pinfunction "2_2") (pintype "passive"))
      (node (ref "U$5") (pin "5") (pinfunction "CMP_5") (pintype "bidirectional"))
    )
    (net (code "178") (name "Net-(U$5-CT)") (class "Default")
      (node (ref "C4") (pin "1") (pinfunction "1_1") (pintype "passive"))
      (node (ref "U$5") (pin "3") (pinfunction "CT_3") (pintype "bidirectional"))
    )
    (net (code "179") (name "Net-(U$18-CMP)") (class "Default")
      (node (ref "C11") (pin "1") (pinfunction "1_1") (pintype "passive"))
      (node (ref "R24") (pin "2") (pinfunction "2_2") (pintype "passive"))
      (node (ref "R25") (pin "1") (pinfunction "1_1") (pintype "passive"))
      (node (ref "R26") (pin "1") (pinfunction "1_1") (pintype "passive"))
      (node (ref "U$18") (pin "5") (pinfunction "CMP_5") (pintype "bidirectional"))
    )
    (net (code "180") (name "Net-(U$18-CT)") (class "Default")
      (node (ref "C10") (pin "1") (pinfunction "1_1") (pintype "passive"))
      (node (ref "U$18") (pin "3") (pinfunction "CT_3") (pintype "bidirectional"))
    )
    (net (code "181") (name "Net-(U1-RX)") (class "Default")
      (node (ref "J1") (pin "2") (pinfunction "2_2") (pintype "passive"))
      (node (ref "U1") (pin "RXD0") (pinfunction "RX_RXD0") (pintype "bidirectional"))
    )
    (net (code "182") (name "Net-(U1-TX)") (class "Default")
      (node (ref "J1") (pin "1") (pinfunction "1_1") (pintype "passive"))
      (node (ref "U1") (pin "TXD0") (pinfunction "TX_TXD0") (pintype "bidirectional"))
    )
    (net (code "183") (name "Net-(U2-BAT{slash}NC)") (class "Default")
      (node (ref "BAT1") (pin "+_1") (pinfunction "+_+_1") (pintype "power_in"))
      (node (ref "J2") (pin "+") (pinfunction "+_+") (pintype "passive"))
      (node (ref "J4") (pin "+") (pinfunction "+_+") (pintype "passive"))
      (node (ref "U2") (pin "3") (pinfunction "BAT/NC_3") (pintype "bidirectional"))
    )
    (net (code "184") (name "Net-(U2-X1)") (class "Default")
      (node (ref "C16") (pin "1") (pinfunction "1_1") (pintype "passive"))
      (node (ref "U2") (pin "1") (pinfunction "X1_1") (pintype "bidirectional"))
      (node (ref "Y1") (pin "P$2") (pinfunction "2_P$2") (pintype "passive"))
    )
    (net (code "185") (name "Net-(U2-X2)") (class "Default")
      (node (ref "C15") (pin "1") (pinfunction "1_1") (pintype "passive"))
      (node (ref "U2") (pin "2") (pinfunction "X2_2") (pintype "bidirectional"))
      (node (ref "Y1") (pin "P$1") (pinfunction "1_P$1") (pintype "passive"))
    )
    (net (code "186") (name "PHOTO") (class "Default")
      (node (ref "R27") (pin "2") (pinfunction "2_2") (pintype "passive"))
      (node (ref "T1") (pin "COL") (pinfunction "C_COL") (pintype "passive"))
      (node (ref "U1") (pin "ADC") (pinfunction "ADC_ADC") (pintype "bidirectional"))
    )
    (net (code "187") (name "VCC") (class "Default")
      (node (ref "C1") (pin "1") (pinfunction "1_1") (pintype "passive"))
      (node (ref "C14") (pin "1") (pinfunction "1_1") (pintype "passive"))
      (node (ref "C2") (pin "1") (pinfunction "1_1") (pintype "passive"))
      (node (ref "C3") (pin "1") (pinfunction "1_1") (pintype "passive"))
      (node (ref "C8") (pin "1") (pinfunction "1_1") (pintype "passive"))
      (node (ref "D4") (pin "C") (pinfunction "C_C") (pintype "passive"))
      (node (ref "R1") (pin "1") (pinfunction "1_1") (pintype "passive"))
      (node (ref "R22") (pin "1") (pinfunction "1_1") (pintype "passive"))
      (node (ref "R23") (pin "1") (pinfunction "1_1") (pintype "passive"))
      (node (ref "R3") (pin "1") (pinfunction "1_1") (pintype "passive"))
      (node (ref "R6") (pin "1") (pinfunction "1_1") (pintype "passive"))
      (node (ref "R9") (pin "1") (pinfunction "1_1") (pintype "passive"))
      (node (ref "U$1") (pin "27") (pinfunction "/POLARITY_27") (pintype "bidirectional"))
      (node (ref "U$1") (pin "30") (pinfunction "VCC_30") (pintype "power_in"))
      (node (ref "U$1") (pin "33") (pinfunction "/BLANK_33") (pintype "bidirectional"))
      (node (ref "U$18") (pin "6") (pinfunction "VCC_6") (pintype "bidirectional"))
      (node (ref "U$2") (pin "27") (pinfunction "/POLARITY_27") (pintype "bidirectional"))
      (node (ref "U$2") (pin "30") (pinfunction "VCC_30") (pintype "power_in"))
      (node (ref "U$2") (pin "33") (pinfunction "/BLANK_33") (pintype "bidirectional"))
      (node (ref "U$5") (pin "6") (pinfunction "VCC_6") (pintype "bidirectional"))
    )
    (net (code "188") (name "V_PULSE") (class "Default")
      (node (ref "D2") (pin "1") (pinfunction "A_1") (pintype "passive"))
      (node (ref "L3") (pin "P$2") (pinfunction "2_P$2") (pintype "passive"))
      (node (ref "Q2") (pin "2") (pinfunction "D_2") (pintype "passive"))
    )
    (net (code "189") (name "unconnected-(N1-PadLHDP)") (class "Default")
      (node (ref "N1") (pin "LHDP") (pinfunction "LHDP_LHDP") (pintype "bidirectional"))
    )
    (net (code "190") (name "unconnected-(N2-PadLHDP)") (class "Default")
      (node (ref "N2") (pin "LHDP") (pinfunction "LHDP_LHDP") (pintype "bidirectional"))
    )
    (net (code "191") (name "unconnected-(N3-PadLHDP)") (class "Default")
      (node (ref "N3") (pin "LHDP") (pinfunction "LHDP_LHDP") (pintype "bidirectional"))
    )
    (net (code "192") (name "unconnected-(N4-PadLHDP)") (class "Default")
      (node (ref "N4") (pin "LHDP") (pinfunction "LHDP_LHDP") (pintype "bidirectional"))
    )
    (net (code "193") (name "unconnected-(N5-PadLHDP)") (class "Default")
      (node (ref "N5") (pin "LHDP") (pinfunction "LHDP_LHDP") (pintype "bidirectional"))
    )
    (net (code "194") (name "unconnected-(N6-PadLHDP)") (class "Default")
      (node (ref "N6") (pin "LHDP") (pinfunction "LHDP_LHDP") (pintype "bidirectional"))
    )
    (net (code "195") (name "unconnected-(P1-A-PadP$1)") (class "Default")
      (node (ref "P1") (pin "P$1") (pinfunction "A_P$1") (pintype "passive"))
    )
    (net (code "196") (name "unconnected-(SV5-Pad11)") (class "Default")
      (node (ref "SV5") (pin "11") (pinfunction "11_11") (pintype "passive"))
    )
    (net (code "197") (name "unconnected-(SV6-Pad11)") (class "Default")
      (node (ref "SV6") (pin "11") (pinfunction "11_11") (pintype "passive"))
    )
    (net (code "198") (name "unconnected-(U$2-DATA_OUT-Pad23)") (class "Default")
      (node (ref "U$2") (pin "23") (pinfunction "DATA_OUT_23") (pintype "bidirectional"))
    )
    (net (code "199") (name "unconnected-(U1-*GPIO9-PadGPIO9)") (class "Default")
      (node (ref "U1") (pin "GPIO9") (pinfunction "*GPIO9_GPIO9") (pintype "bidirectional"))
    )
    (net (code "200") (name "unconnected-(U1-*GPIO10-PadGPIO10)") (class "Default")
      (node (ref "U1") (pin "GPIO10") (pinfunction "*GPIO10_GPIO10") (pintype "bidirectional"))
    )
    (net (code "201") (name "unconnected-(U1-PadCS0)") (class "Default")
      (node (ref "U1") (pin "CS0") (pinfunction "CS0_CS0") (pintype "bidirectional"))
    )
    (net (code "202") (name "unconnected-(U1-PadMISO)") (class "Default")
      (node (ref "U1") (pin "MISO") (pinfunction "MISO_MISO") (pintype "bidirectional"))
    )
    (net (code "203") (name "unconnected-(U1-PadMOSI)") (class "Default")
      (node (ref "U1") (pin "MOSI") (pinfunction "MOSI_MOSI") (pintype "bidirectional"))
    )
    (net (code "204") (name "unconnected-(U1-PadSCLK)") (class "Default")
      (node (ref "U1") (pin "SCLK") (pinfunction "SCLK_SCLK") (pintype "bidirectional"))
    )
    (net (code "205") (name "unconnected-(U2-MFP-Pad7)") (class "Default")
      (node (ref "U2") (pin "7") (pinfunction "MFP_7") (pintype "bidirectional"))
    )
  )
)
